# Microprocessor.net
KiCad netlist of a schematic drawn in Altium Designer
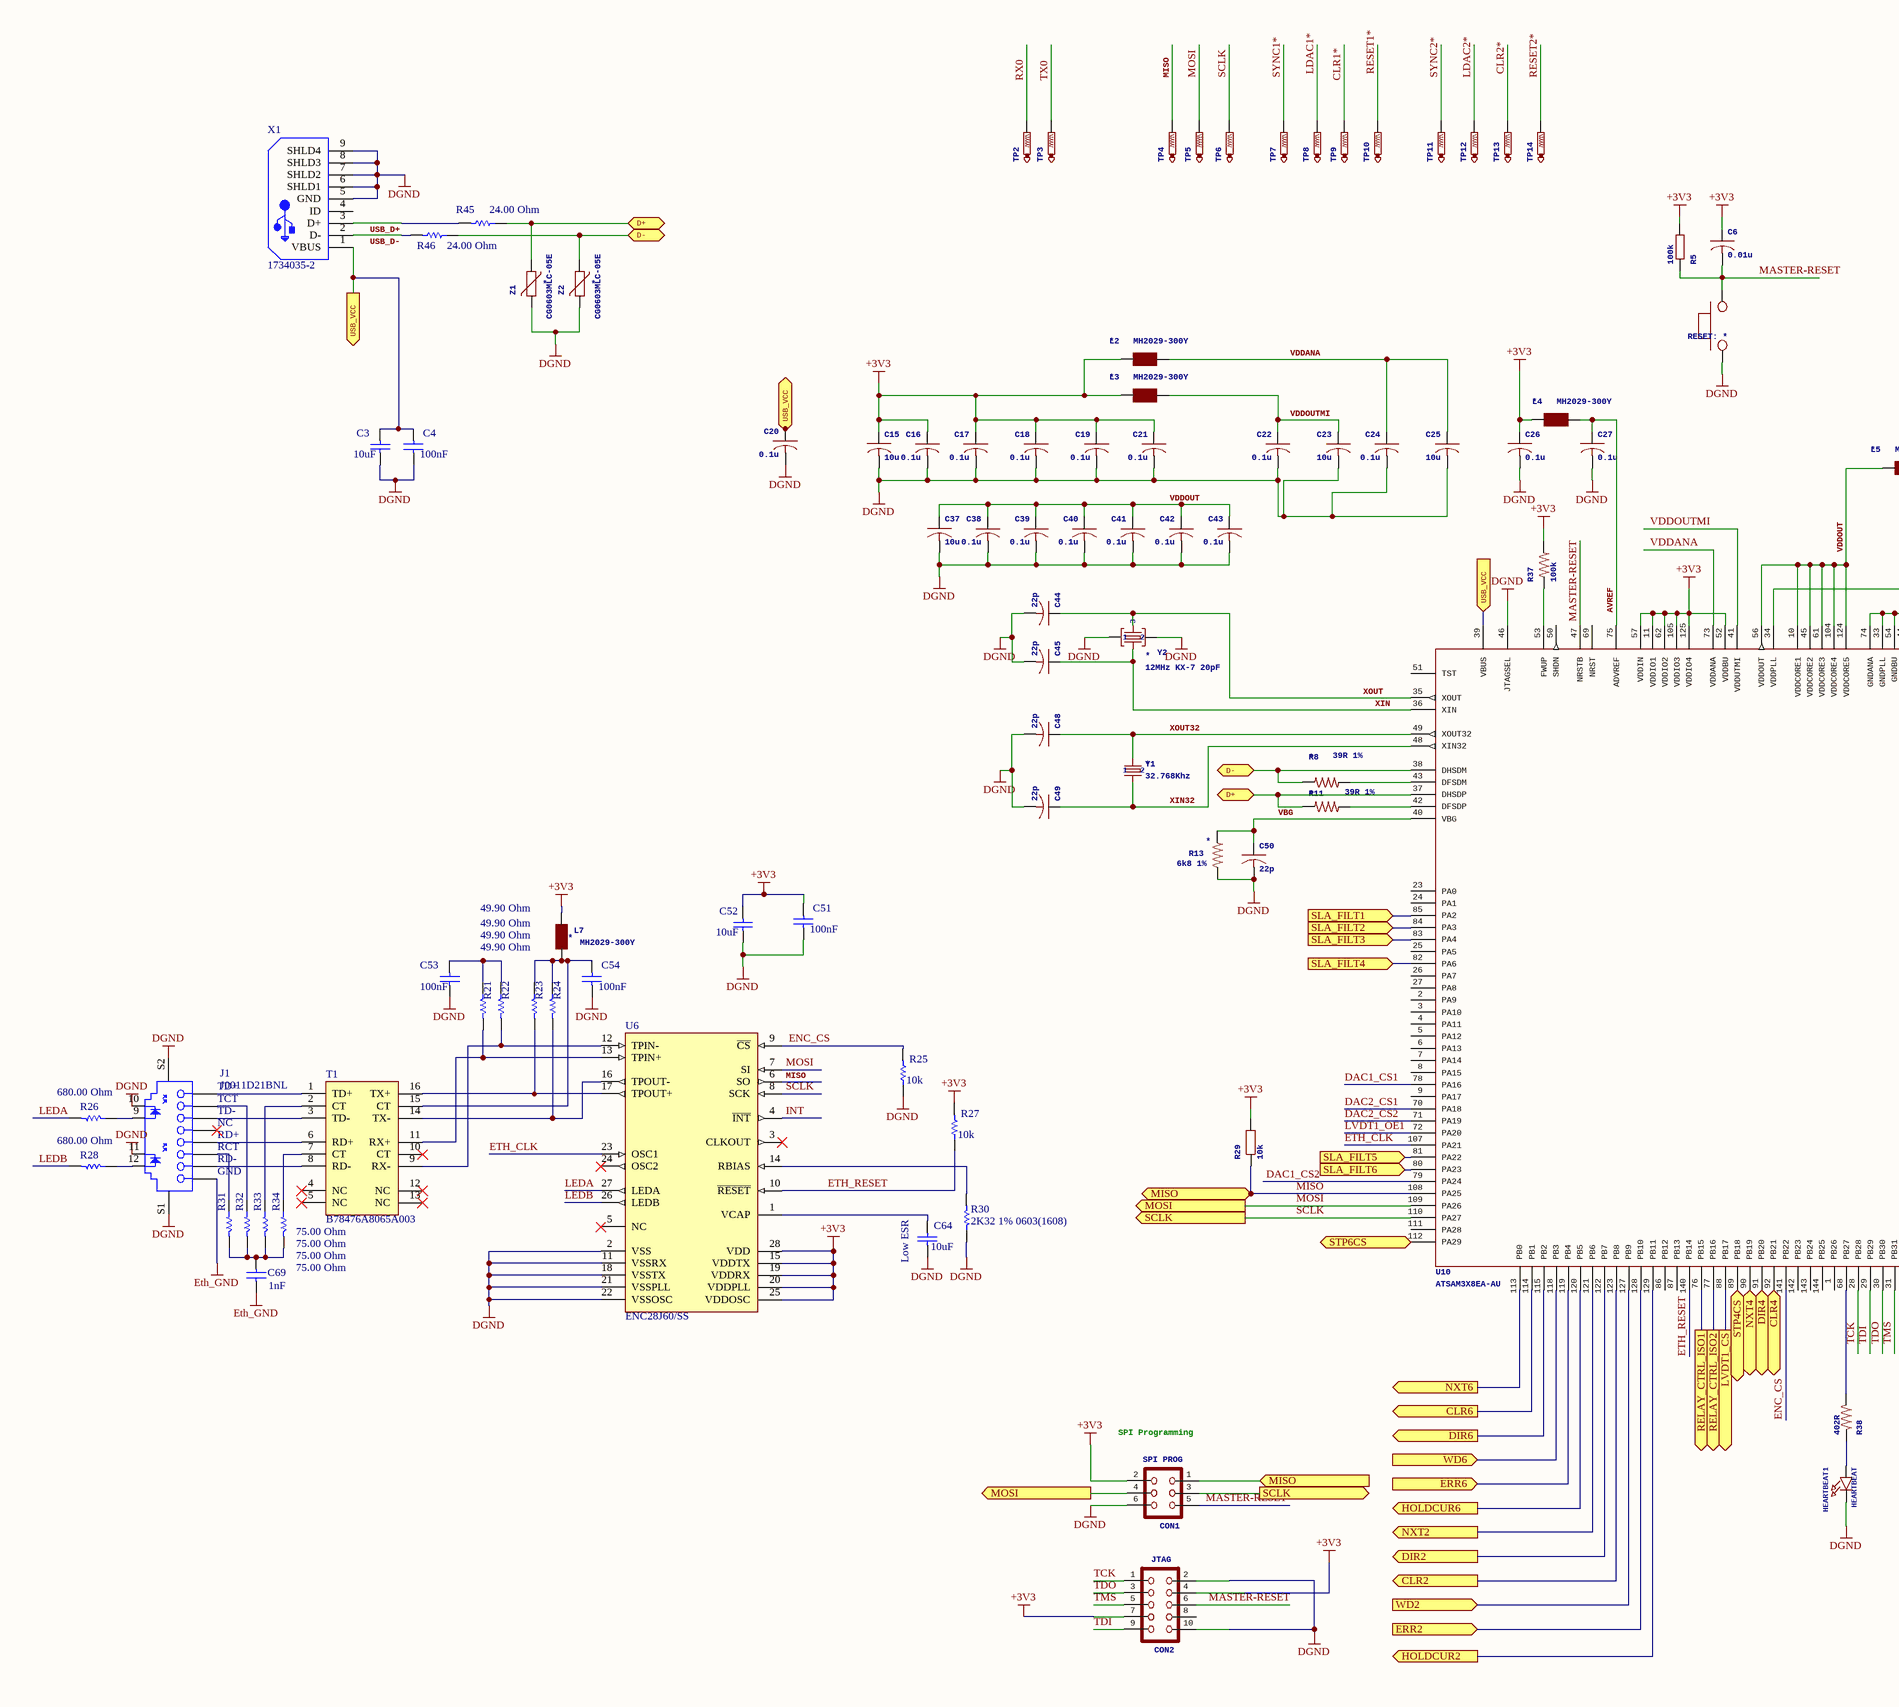
[diagram p0: Microprocessor.SchDoc, left]
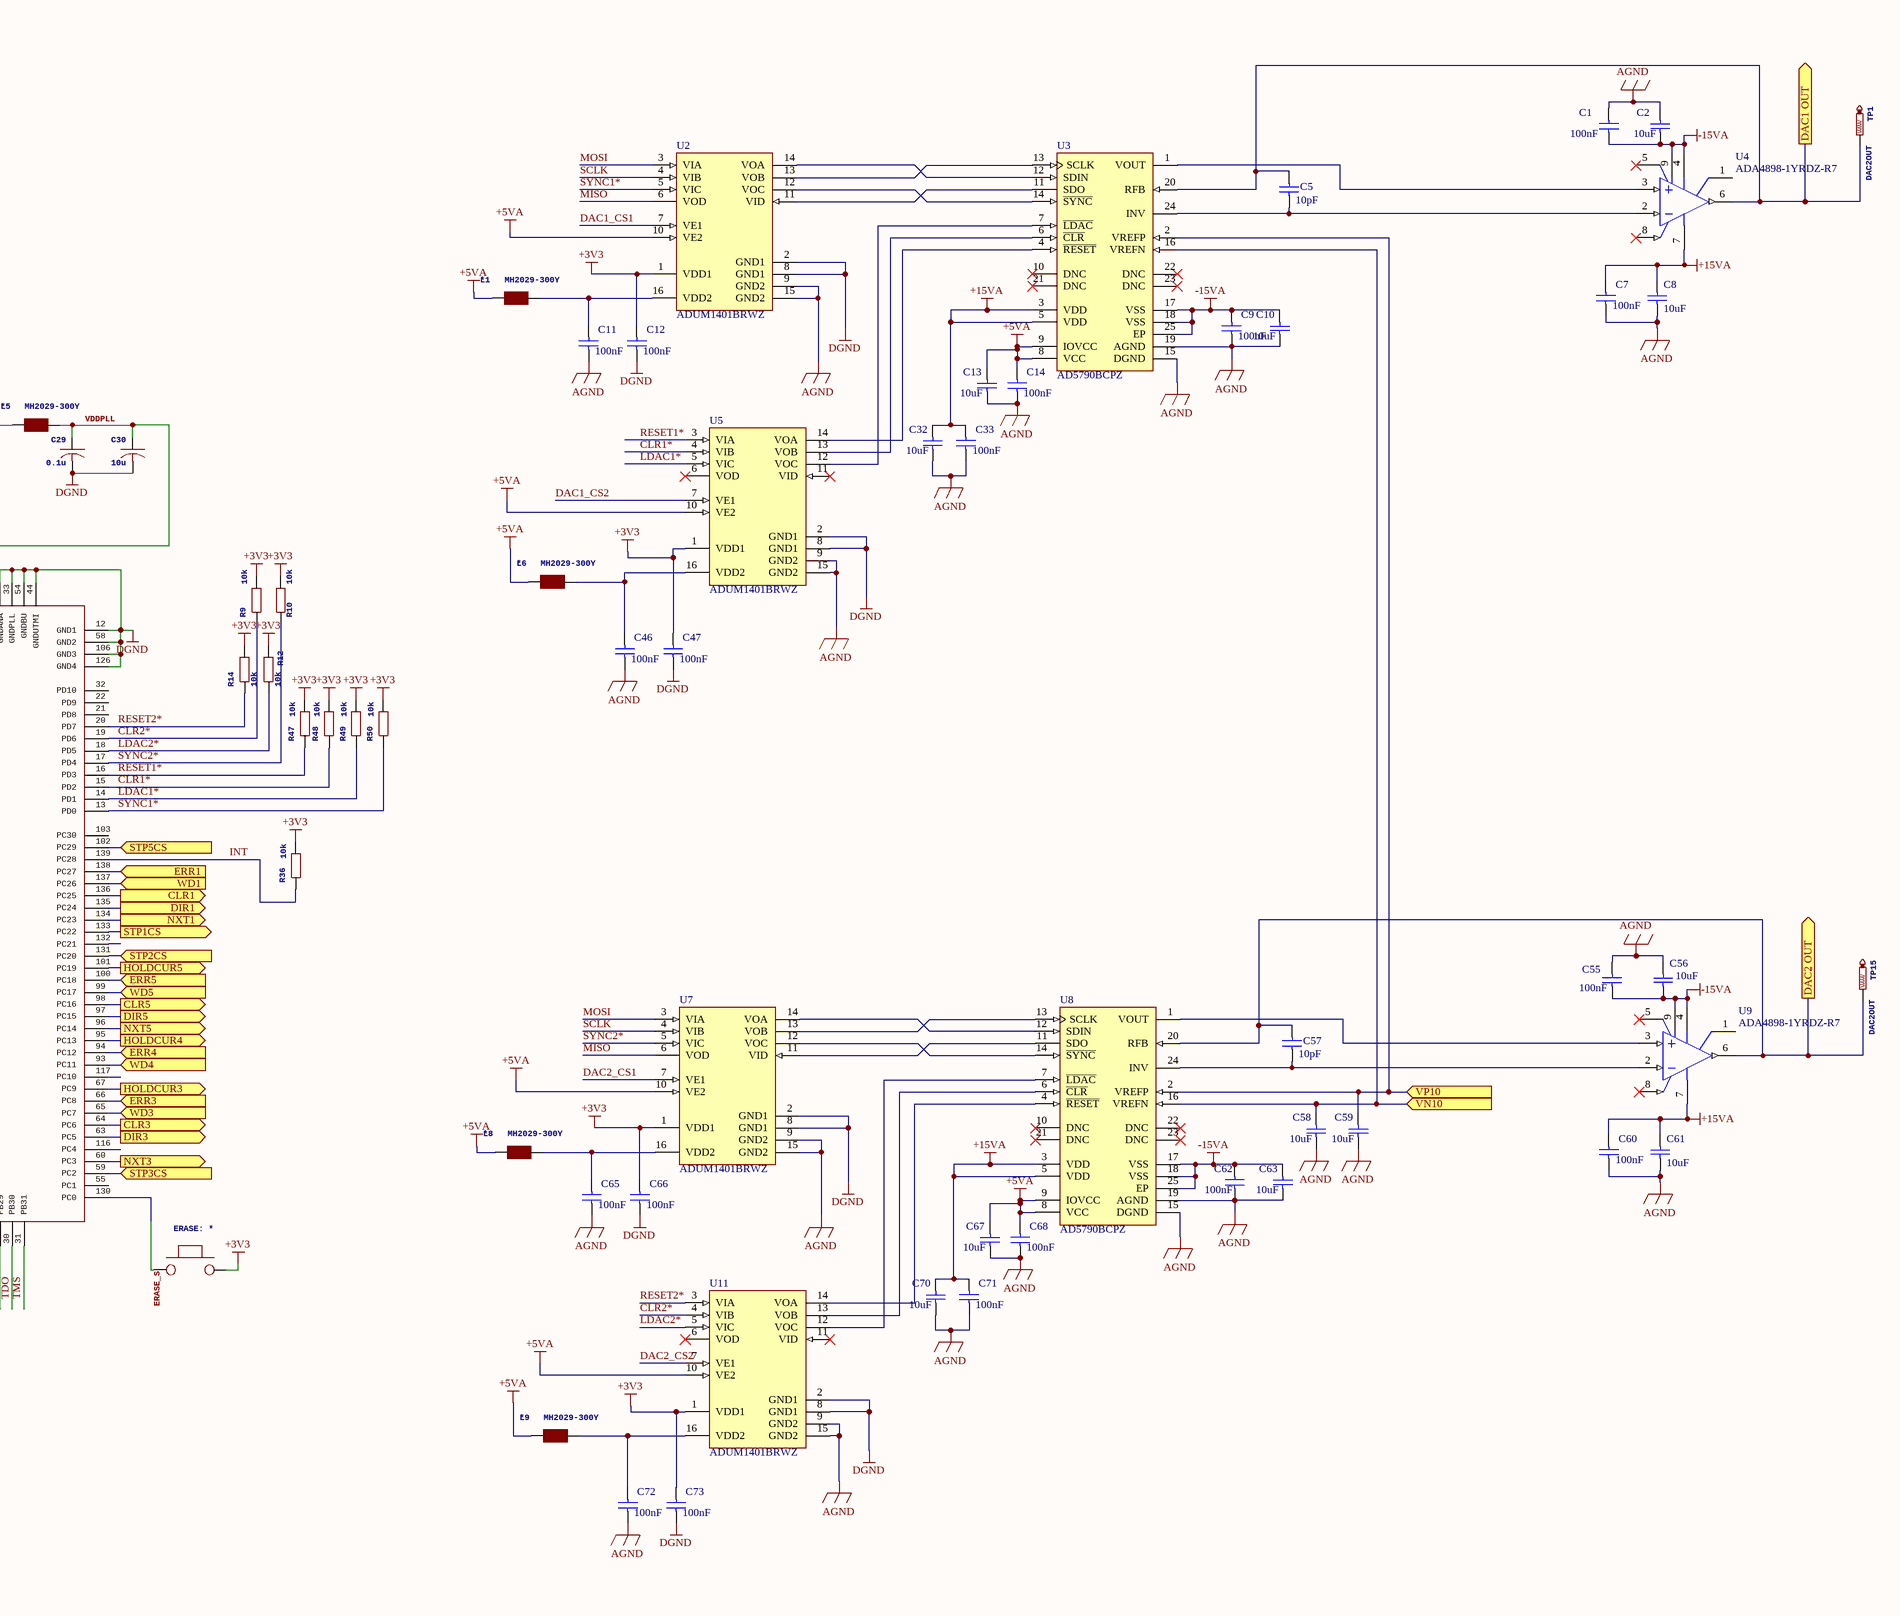
[diagram p1: Microprocessor.SchDoc, right]

(export (version "E")
  (design (tool "Eeschema 10.0.6"))
  (components
    (comp (ref "C1")
      (value "100nF")
      (footprint "CAPC0603(1608)100_N")
      (description "CAP 100nF 25V ±5% 0603 (1608 Metric) Thickness 1mm SMD")
      (fields (field (name "TOLERANCE") "Â±5%") (field (name "Comment") "CAP 100nF 25V 0603(1608)"))
      (libsource (lib "Altium Content Vault") (part "CMP-1035-02587-1"))
    )
    (comp (ref "C2")
      (value "10uF")
      (footprint "CAPC0805(2012)145_N")
      (description "CAP 10uF 6.3V -20% to +80% 0805 (2012 Metric) Thickness 1.45mm SMD")
      (fields (field (name "TOLERANCE") "-20% to +80%") (field (name "Comment") "CAP 10uF 6.3V 0805(2012)"))
      (libsource (lib "Altium Content Vault") (part "CMP-1036-04921-1"))
    )
    (comp (ref "C3")
      (value "10uF")
      (footprint "CAPC0805(2012)145_N")
      (description "CAP 10uF 6.3V -20% to +80% 0805 (2012 Metric) Thickness 1.45mm SMD")
      (fields (field (name "TOLERANCE") "-20% to +80%") (field (name "Comment") "CAP 10uF 6.3V 0805(2012)"))
      (libsource (lib "Altium Content Vault") (part "CMP-1036-04921-1"))
    )
    (comp (ref "C4")
      (value "100nF")
      (footprint "CAPC0603(1608)100_N")
      (description "CAP 100nF 25V ±5% 0603 (1608 Metric) Thickness 1mm SMD")
      (fields (field (name "TOLERANCE") "Â±5%") (field (name "Comment") "CAP 100nF 25V 0603(1608)"))
      (libsource (lib "Altium Content Vault") (part "CMP-1035-02587-1"))
    )
    (comp (ref "C5")
      (value "10pF")
      (footprint "CAPC0805(2012)100_M")
      (description "CAP 10pF 25V ±0.25pF 0805 (2012 Metric) Thickness 1mm SMD")
      (fields (field (name "TOLERANCE") "Â±0.25pF") (field (name "Comment") "CAP 10pF 25V 0805(2012)"))
      (libsource (lib "Altium Content Vault") (part "CMP-1036-00839-1"))
    )
    (comp (ref "C6")
      (value "0.01u")
      (footprint "C0805")
      (description "CAPACITOR, American symbol")
      (libsource (lib "") (part "C-USC0805_1"))
    )
    (comp (ref "C7")
      (value "100nF")
      (footprint "CAPC0603(1608)100_N")
      (description "CAP 100nF 25V ±5% 0603 (1608 Metric) Thickness 1mm SMD")
      (fields (field (name "TOLERANCE") "Â±5%") (field (name "Comment") "CAP 100nF 25V 0603(1608)"))
      (libsource (lib "Altium Content Vault") (part "CMP-1035-02587-1"))
    )
    (comp (ref "C8")
      (value "10uF")
      (footprint "CAPC0805(2012)145_N")
      (description "CAP 10uF 6.3V -20% to +80% 0805 (2012 Metric) Thickness 1.45mm SMD")
      (fields (field (name "TOLERANCE") "-20% to +80%") (field (name "Comment") "CAP 10uF 6.3V 0805(2012)"))
      (libsource (lib "Altium Content Vault") (part "CMP-1036-04921-1"))
    )
    (comp (ref "C9")
      (value "100nF")
      (footprint "CAPC0603(1608)100_N")
      (description "CAP 100nF 25V ±5% 0603 (1608 Metric) Thickness 1mm SMD")
      (fields (field (name "TOLERANCE") "Â±5%") (field (name "Comment") "CAP 100nF 25V 0603(1608)"))
      (libsource (lib "Altium Content Vault") (part "CMP-1035-02587-1"))
    )
    (comp (ref "C10")
      (value "10uF")
      (footprint "CAPC0805(2012)145_N")
      (description "CAP 10uF 6.3V -20% to +80% 0805 (2012 Metric) Thickness 1.45mm SMD")
      (fields (field (name "TOLERANCE") "-20% to +80%") (field (name "Comment") "CAP 10uF 6.3V 0805(2012)"))
      (libsource (lib "Altium Content Vault") (part "CMP-1036-04921-1"))
    )
    (comp (ref "C11")
      (value "100nF")
      (footprint "CAPC0603(1608)100_N")
      (description "CAP 100nF 25V ±5% 0603 (1608 Metric) Thickness 1mm SMD")
      (fields (field (name "TOLERANCE") "Â±5%") (field (name "Comment") "CAP 100nF 25V 0603(1608)"))
      (libsource (lib "Altium Content Vault") (part "CMP-1035-02587-1"))
    )
    (comp (ref "C12")
      (value "100nF")
      (footprint "CAPC0603(1608)100_N")
      (description "CAP 100nF 25V ±5% 0603 (1608 Metric) Thickness 1mm SMD")
      (fields (field (name "TOLERANCE") "Â±5%") (field (name "Comment") "CAP 100nF 25V 0603(1608)"))
      (libsource (lib "Altium Content Vault") (part "CMP-1035-02587-1"))
    )
    (comp (ref "C13")
      (value "10uF")
      (footprint "CAPC0805(2012)145_N")
      (description "CAP 10uF 6.3V -20% to +80% 0805 (2012 Metric) Thickness 1.45mm SMD")
      (fields (field (name "TOLERANCE") "-20% to +80%") (field (name "Comment") "CAP 10uF 6.3V 0805(2012)"))
      (libsource (lib "Altium Content Vault") (part "CMP-1036-04921-1"))
    )
    (comp (ref "C14")
      (value "100nF")
      (footprint "CAPC0603(1608)100_N")
      (description "CAP 100nF 25V ±5% 0603 (1608 Metric) Thickness 1mm SMD")
      (fields (field (name "TOLERANCE") "Â±5%") (field (name "Comment") "CAP 100nF 25V 0603(1608)"))
      (libsource (lib "Altium Content Vault") (part "CMP-1035-02587-1"))
    )
    (comp (ref "C15")
      (value "10u")
      (footprint "C0805")
      (description "CAPACITOR, American symbol")
      (libsource (lib "") (part "C-USC0805_1"))
    )
    (comp (ref "C16")
      (value "0.1u")
      (footprint "C0805")
      (description "CAPACITOR, American symbol")
      (libsource (lib "rcl") (part "C-USC0805"))
    )
    (comp (ref "C17")
      (value "0.1u")
      (footprint "C0805")
      (description "CAPACITOR, American symbol")
      (libsource (lib "rcl") (part "C-USC0805"))
    )
    (comp (ref "C18")
      (value "0.1u")
      (footprint "C0805")
      (description "CAPACITOR, American symbol")
      (libsource (lib "rcl") (part "C-USC0805"))
    )
    (comp (ref "C19")
      (value "0.1u")
      (footprint "C0805")
      (description "CAPACITOR, American symbol")
      (libsource (lib "rcl") (part "C-USC0805"))
    )
    (comp (ref "C20")
      (value "0.1u")
      (footprint "C0805")
      (description "CAPACITOR, American symbol")
      (libsource (lib "rcl") (part "C-USC0805"))
    )
    (comp (ref "C21")
      (value "0.1u")
      (footprint "C0805")
      (description "CAPACITOR, American symbol")
      (libsource (lib "rcl") (part "C-USC0805"))
    )
    (comp (ref "C22")
      (value "0.1u")
      (footprint "C0805")
      (description "CAPACITOR, American symbol")
      (libsource (lib "rcl") (part "C-USC0805"))
    )
    (comp (ref "C23")
      (value "10u")
      (footprint "C0805")
      (description "CAPACITOR, American symbol")
      (libsource (lib "rcl") (part "C-USC0805"))
    )
    (comp (ref "C24")
      (value "0.1u")
      (footprint "C0805")
      (description "CAPACITOR, American symbol")
      (libsource (lib "rcl") (part "C-USC0805"))
    )
    (comp (ref "C25")
      (value "10u")
      (footprint "C0805")
      (description "CAPACITOR, American symbol")
      (libsource (lib "rcl") (part "C-USC0805"))
    )
    (comp (ref "C26")
      (value "0.1u")
      (footprint "C0805")
      (description "CAPACITOR, American symbol")
      (libsource (lib "") (part "C-USC0805_1"))
    )
    (comp (ref "C27")
      (value "0.1u")
      (footprint "C0805")
      (description "CAPACITOR, American symbol")
      (libsource (lib "") (part "C-USC0805_1"))
    )
    (comp (ref "C29")
      (value "0.1u")
      (footprint "C0805")
      (description "CAPACITOR, American symbol")
      (libsource (lib "rcl") (part "C-USC0805"))
    )
    (comp (ref "C30")
      (value "10u")
      (footprint "C0805")
      (description "CAPACITOR, American symbol")
      (libsource (lib "rcl") (part "C-USC0805"))
    )
    (comp (ref "C32")
      (value "10uF")
      (footprint "CAPC0805(2012)145_N")
      (description "CAP 10uF 6.3V -20% to +80% 0805 (2012 Metric) Thickness 1.45mm SMD")
      (fields (field (name "TOLERANCE") "-20% to +80%") (field (name "Comment") "CAP 10uF 6.3V 0805(2012)"))
      (libsource (lib "Altium Content Vault") (part "CMP-1036-04921-1"))
    )
    (comp (ref "C33")
      (value "100nF")
      (footprint "CAPC0603(1608)100_N")
      (description "CAP 100nF 25V ±5% 0603 (1608 Metric) Thickness 1mm SMD")
      (fields (field (name "TOLERANCE") "Â±5%") (field (name "Comment") "CAP 100nF 25V 0603(1608)"))
      (libsource (lib "Altium Content Vault") (part "CMP-1035-02587-1"))
    )
    (comp (ref "C37")
      (value "10u")
      (footprint "C0805")
      (description "CAPACITOR, American symbol")
      (libsource (lib "") (part "C-USC0805_1"))
    )
    (comp (ref "C38")
      (value "0.1u")
      (footprint "C0805")
      (description "CAPACITOR, American symbol")
      (libsource (lib "rcl") (part "C-USC0805"))
    )
    (comp (ref "C39")
      (value "0.1u")
      (footprint "C0805")
      (description "CAPACITOR, American symbol")
      (libsource (lib "rcl") (part "C-USC0805"))
    )
    (comp (ref "C40")
      (value "0.1u")
      (footprint "C0805")
      (description "CAPACITOR, American symbol")
      (libsource (lib "rcl") (part "C-USC0805"))
    )
    (comp (ref "C41")
      (value "0.1u")
      (footprint "C0805")
      (description "CAPACITOR, American symbol")
      (libsource (lib "rcl") (part "C-USC0805"))
    )
    (comp (ref "C42")
      (value "0.1u")
      (footprint "C0805")
      (description "CAPACITOR, American symbol")
      (libsource (lib "rcl") (part "C-USC0805"))
    )
    (comp (ref "C43")
      (value "0.1u")
      (footprint "C0805")
      (description "CAPACITOR, American symbol")
      (libsource (lib "rcl") (part "C-USC0805"))
    )
    (comp (ref "C44")
      (value "22p")
      (footprint "C1206")
      (description "CAPACITOR, American symbol")
      (libsource (lib "rcl") (part "C-USC1206"))
    )
    (comp (ref "C45")
      (value "22p")
      (footprint "C1206")
      (description "CAPACITOR, American symbol")
      (libsource (lib "rcl") (part "C-USC1206"))
    )
    (comp (ref "C46")
      (value "100nF")
      (footprint "CAPC0603(1608)100_N")
      (description "CAP 100nF 25V ±5% 0603 (1608 Metric) Thickness 1mm SMD")
      (fields (field (name "TOLERANCE") "Â±5%") (field (name "Comment") "CAP 100nF 25V 0603(1608)"))
      (libsource (lib "Altium Content Vault") (part "CMP-1035-02587-1"))
    )
    (comp (ref "C47")
      (value "100nF")
      (footprint "CAPC0603(1608)100_N")
      (description "CAP 100nF 25V ±5% 0603 (1608 Metric) Thickness 1mm SMD")
      (fields (field (name "TOLERANCE") "Â±5%") (field (name "Comment") "CAP 100nF 25V 0603(1608)"))
      (libsource (lib "Altium Content Vault") (part "CMP-1035-02587-1"))
    )
    (comp (ref "C48")
      (value "22p")
      (footprint "C0805")
      (description "CAPACITOR, American symbol")
      (libsource (lib "rcl") (part "C-USC0805"))
    )
    (comp (ref "C49")
      (value "22p")
      (footprint "C0805")
      (description "CAPACITOR, American symbol")
      (libsource (lib "rcl") (part "C-USC0805"))
    )
    (comp (ref "C50")
      (value "22p")
      (footprint "C0805")
      (description "CAPACITOR, American symbol")
      (libsource (lib "") (part "C-USC0805_1"))
    )
    (comp (ref "C51")
      (value "100nF")
      (footprint "CAPC0603(1608)100_N")
      (description "CAP 100nF 25V ±5% 0603 (1608 Metric) Thickness 1mm SMD")
      (fields (field (name "TOLERANCE") "Â±5%") (field (name "Comment") "CAP 100nF 25V 0603(1608)"))
      (libsource (lib "Altium Content Vault") (part "CMP-1035-02587-1"))
    )
    (comp (ref "C52")
      (value "10uF")
      (footprint "CAPC0805(2012)145_N")
      (description "CAP 10uF 6.3V -20% to +80% 0805 (2012 Metric) Thickness 1.45mm SMD")
      (fields (field (name "TOLERANCE") "-20% to +80%") (field (name "Comment") "CAP 10uF 6.3V 0805(2012)"))
      (libsource (lib "Altium Content Vault") (part "CMP-1036-04921-1"))
    )
    (comp (ref "C53")
      (value "100nF")
      (footprint "CAPC0603(1608)100_N")
      (description "CAP 100nF 25V ±5% 0603 (1608 Metric) Thickness 1mm SMD")
      (fields (field (name "TOLERANCE") "Â±5%") (field (name "Comment") "CAP 100nF 25V 0603(1608)"))
      (libsource (lib "Altium Content Vault") (part "CMP-1035-02587-1"))
    )
    (comp (ref "C54")
      (value "100nF")
      (footprint "CAPC0603(1608)100_N")
      (description "CAP 100nF 25V ±5% 0603 (1608 Metric) Thickness 1mm SMD")
      (fields (field (name "TOLERANCE") "Â±5%") (field (name "Comment") "CAP 100nF 25V 0603(1608)"))
      (libsource (lib "Altium Content Vault") (part "CMP-1035-02587-1"))
    )
    (comp (ref "C55")
      (value "100nF")
      (footprint "CAPC0603(1608)100_N")
      (description "CAP 100nF 25V ±5% 0603 (1608 Metric) Thickness 1mm SMD")
      (fields (field (name "TOLERANCE") "Â±5%") (field (name "Comment") "CAP 100nF 25V 0603(1608)"))
      (libsource (lib "Altium Content Vault") (part "CMP-1035-02587-1"))
    )
    (comp (ref "C56")
      (value "10uF")
      (footprint "CAPC0805(2012)145_N")
      (description "CAP 10uF 6.3V -20% to +80% 0805 (2012 Metric) Thickness 1.45mm SMD")
      (fields (field (name "TOLERANCE") "-20% to +80%") (field (name "Comment") "CAP 10uF 6.3V 0805(2012)"))
      (libsource (lib "Altium Content Vault") (part "CMP-1036-04921-1"))
    )
    (comp (ref "C57")
      (value "10pF")
      (footprint "CAPC0805(2012)100_M")
      (description "CAP 10pF 25V ±0.25pF 0805 (2012 Metric) Thickness 1mm SMD")
      (fields (field (name "TOLERANCE") "Â±0.25pF") (field (name "Comment") "CAP 10pF 25V 0805(2012)"))
      (libsource (lib "Altium Content Vault") (part "CMP-1036-00839-1"))
    )
    (comp (ref "C58")
      (value "10uF")
      (footprint "CAPC0805(2012)145_N")
      (description "CAP 10uF 6.3V -20% to +80% 0805 (2012 Metric) Thickness 1.45mm SMD")
      (fields (field (name "TOLERANCE") "-20% to +80%") (field (name "Comment") "CAP 10uF 6.3V 0805(2012)"))
      (libsource (lib "Altium Content Vault") (part "CMP-1036-04921-1"))
    )
    (comp (ref "C59")
      (value "10uF")
      (footprint "CAPC0805(2012)145_N")
      (description "CAP 10uF 6.3V -20% to +80% 0805 (2012 Metric) Thickness 1.45mm SMD")
      (fields (field (name "TOLERANCE") "-20% to +80%") (field (name "Comment") "CAP 10uF 6.3V 0805(2012)"))
      (libsource (lib "Altium Content Vault") (part "CMP-1036-04921-1"))
    )
    (comp (ref "C60")
      (value "100nF")
      (footprint "CAPC0603(1608)100_N")
      (description "CAP 100nF 25V ±5% 0603 (1608 Metric) Thickness 1mm SMD")
      (fields (field (name "TOLERANCE") "Â±5%") (field (name "Comment") "CAP 100nF 25V 0603(1608)"))
      (libsource (lib "Altium Content Vault") (part "CMP-1035-02587-1"))
    )
    (comp (ref "C61")
      (value "10uF")
      (footprint "CAPC0805(2012)145_N")
      (description "CAP 10uF 6.3V -20% to +80% 0805 (2012 Metric) Thickness 1.45mm SMD")
      (fields (field (name "TOLERANCE") "-20% to +80%") (field (name "Comment") "CAP 10uF 6.3V 0805(2012)"))
      (libsource (lib "Altium Content Vault") (part "CMP-1036-04921-1"))
    )
    (comp (ref "C62")
      (value "100nF")
      (footprint "CAPC0603(1608)100_N")
      (description "CAP 100nF 25V ±5% 0603 (1608 Metric) Thickness 1mm SMD")
      (fields (field (name "TOLERANCE") "Â±5%") (field (name "Comment") "CAP 100nF 25V 0603(1608)"))
      (libsource (lib "Altium Content Vault") (part "CMP-1035-02587-1"))
    )
    (comp (ref "C63")
      (value "10uF")
      (footprint "CAPC0805(2012)145_N")
      (description "CAP 10uF 6.3V -20% to +80% 0805 (2012 Metric) Thickness 1.45mm SMD")
      (fields (field (name "TOLERANCE") "-20% to +80%") (field (name "Comment") "CAP 10uF 6.3V 0805(2012)"))
      (libsource (lib "Altium Content Vault") (part "CMP-1036-04921-1"))
    )
    (comp (ref "C64")
      (value "10uF")
      (footprint "CAPC1206(3216)190_M")
      (description "CAP 10uF 6.3V -20% to +80% 1206 (3216 Metric) Thickness 1.9mm SMD")
      (fields (field (name "TOLERANCE") "-20% to +80%") (field (name "Comment") "CAP 10uF 6.3V 1206(3216)"))
      (libsource (lib "Altium Content Vault") (part "CMP-1037-04965-1"))
    )
    (comp (ref "C65")
      (value "100nF")
      (footprint "CAPC0603(1608)100_N")
      (description "CAP 100nF 25V ±5% 0603 (1608 Metric) Thickness 1mm SMD")
      (fields (field (name "TOLERANCE") "Â±5%") (field (name "Comment") "CAP 100nF 25V 0603(1608)"))
      (libsource (lib "Altium Content Vault") (part "CMP-1035-02587-1"))
    )
    (comp (ref "C66")
      (value "100nF")
      (footprint "CAPC0603(1608)100_N")
      (description "CAP 100nF 25V ±5% 0603 (1608 Metric) Thickness 1mm SMD")
      (fields (field (name "TOLERANCE") "Â±5%") (field (name "Comment") "CAP 100nF 25V 0603(1608)"))
      (libsource (lib "Altium Content Vault") (part "CMP-1035-02587-1"))
    )
    (comp (ref "C67")
      (value "10uF")
      (footprint "CAPC0805(2012)145_N")
      (description "CAP 10uF 6.3V -20% to +80% 0805 (2012 Metric) Thickness 1.45mm SMD")
      (fields (field (name "TOLERANCE") "-20% to +80%") (field (name "Comment") "CAP 10uF 6.3V 0805(2012)"))
      (libsource (lib "Altium Content Vault") (part "CMP-1036-04921-1"))
    )
    (comp (ref "C68")
      (value "100nF")
      (footprint "CAPC0603(1608)100_N")
      (description "CAP 100nF 25V ±5% 0603 (1608 Metric) Thickness 1mm SMD")
      (fields (field (name "TOLERANCE") "Â±5%") (field (name "Comment") "CAP 100nF 25V 0603(1608)"))
      (libsource (lib "Altium Content Vault") (part "CMP-1035-02587-1"))
    )
    (comp (ref "C69")
      (value "1206GC102KAZ1A")
      (footprint "CAPC3317X180X60LL30T20")
      (description "Chip Capacitor, 1 nF, +/- 10%, 2000 V, -55 to 125 degC, 1206 (3216 Metric), RoHS, Tape and Reel")
      (fields (field (name "MANUFACTURER") "AVX") (field (name "CAPACITANCE") "1nF"))
      (libsource (lib "Altium Content Vault") (part "CMP-2000-05469-1"))
    )
    (comp (ref "C70")
      (value "10uF")
      (footprint "CAPC0805(2012)145_N")
      (description "CAP 10uF 6.3V -20% to +80% 0805 (2012 Metric) Thickness 1.45mm SMD")
      (fields (field (name "TOLERANCE") "-20% to +80%") (field (name "Comment") "CAP 10uF 6.3V 0805(2012)"))
      (libsource (lib "Altium Content Vault") (part "CMP-1036-04921-1"))
    )
    (comp (ref "C71")
      (value "100nF")
      (footprint "CAPC0603(1608)100_N")
      (description "CAP 100nF 25V ±5% 0603 (1608 Metric) Thickness 1mm SMD")
      (fields (field (name "TOLERANCE") "Â±5%") (field (name "Comment") "CAP 100nF 25V 0603(1608)"))
      (libsource (lib "Altium Content Vault") (part "CMP-1035-02587-1"))
    )
    (comp (ref "C72")
      (value "100nF")
      (footprint "CAPC0603(1608)100_N")
      (description "CAP 100nF 25V ±5% 0603 (1608 Metric) Thickness 1mm SMD")
      (fields (field (name "TOLERANCE") "Â±5%") (field (name "Comment") "CAP 100nF 25V 0603(1608)"))
      (libsource (lib "Altium Content Vault") (part "CMP-1035-02587-1"))
    )
    (comp (ref "C73")
      (value "100nF")
      (footprint "CAPC0603(1608)100_N")
      (description "CAP 100nF 25V ±5% 0603 (1608 Metric) Thickness 1mm SMD")
      (fields (field (name "TOLERANCE") "Â±5%") (field (name "Comment") "CAP 100nF 25V 0603(1608)"))
      (libsource (lib "Altium Content Vault") (part "CMP-1035-02587-1"))
    )
    (comp (ref "CON1")
      (value "SPI PROG")
      (footprint "CON06")
      (description "CONNECTOR")
      (libsource (lib "con-harting") (part "CON06"))
    )
    (comp (ref "CON2")
      (value "JTAG")
      (footprint "CON10")
      (description "CONNECTOR")
      (libsource (lib "con-harting") (part "CON10"))
    )
    (comp (ref "ERASE1")
      (value "PUCHBUTTON")
      (footprint "PUCHBUTTON")
      (fields (field (name "ERASE") "*"))
      (libsource (lib "PushButton") (part "PUCHBUTTON"))
    )
    (comp (ref "HEARTBEAT1")
      (value "HEARTBEAT")
      (footprint "CHIPLED_0805")
      (libsource (lib "microbuilder") (part "LED0805"))
    )
    (comp (ref "J1")
      (value "J0011D21BNL")
      (footprint "PULS-J00XXD21XNL-B-12")
      (fields (field (name "MANUFACTURER") "Pulse"))
      (libsource (lib "Altium Content Vault") (part "CMP-2000-05321-1"))
    )
    (comp (ref "L1")
      (value "MH2029-300Y")
      (footprint "0805")
      (fields (field (name "NAME") "*"))
      (libsource (lib "") (part "WE-CBF_0805_1"))
    )
    (comp (ref "L2")
      (value "MH2029-300Y")
      (footprint "0805")
      (fields (field (name "NAME") "*"))
      (libsource (lib "") (part "WE-CBF_0805_1"))
    )
    (comp (ref "L3")
      (value "MH2029-300Y")
      (footprint "0805")
      (fields (field (name "NAME") "*"))
      (libsource (lib "") (part "WE-CBF_0805_1"))
    )
    (comp (ref "L4")
      (value "MH2029-300Y")
      (footprint "0805")
      (fields (field (name "NAME") "*"))
      (libsource (lib "") (part "WE-CBF_0805_1"))
    )
    (comp (ref "L5")
      (value "MH2029-300Y")
      (footprint "0805")
      (fields (field (name "NAME") "*"))
      (libsource (lib "") (part "WE-CBF_0805_1"))
    )
    (comp (ref "L6")
      (value "MH2029-300Y")
      (footprint "0805")
      (fields (field (name "NAME") "*"))
      (libsource (lib "") (part "WE-CBF_0805_1"))
    )
    (comp (ref "L7")
      (value "MH2029-300Y")
      (footprint "0805")
      (fields (field (name "NAME") "*"))
      (libsource (lib "wuerth-elektronik") (part "WE-CBF_0805"))
    )
    (comp (ref "L8")
      (value "MH2029-300Y")
      (footprint "0805")
      (fields (field (name "NAME") "*"))
      (libsource (lib "") (part "WE-CBF_0805_1"))
    )
    (comp (ref "L9")
      (value "MH2029-300Y")
      (footprint "0805")
      (fields (field (name "NAME") "*"))
      (libsource (lib "") (part "WE-CBF_0805_1"))
    )
    (comp (ref "R5")
      (value "100k")
      (footprint "R0603")
      (description "RESISTOR, European symbol")
      (libsource (lib "rcl") (part "R-EU_R0603"))
    )
    (comp (ref "R8")
      (value "39R 1%")
      (footprint "R0805")
      (description "RESISTOR, American symbol")
      (fields (field (name "NAME") "*"))
      (libsource (lib "rcl") (part "R-US_R0805"))
    )
    (comp (ref "R9")
      (value "10k")
      (footprint "R0603")
      (description "RESISTOR, European symbol")
      (libsource (lib "rcl") (part "R-EU_R0603"))
    )
    (comp (ref "R10")
      (value "10k")
      (footprint "R0603")
      (description "RESISTOR, European symbol")
      (libsource (lib "rcl") (part "R-EU_R0603"))
    )
    (comp (ref "R11")
      (value "39R 1%")
      (footprint "R0805")
      (description "RESISTOR, American symbol")
      (fields (field (name "NAME") "*"))
      (libsource (lib "rcl") (part "R-US_R0805"))
    )
    (comp (ref "R12")
      (value "10k")
      (footprint "R0603")
      (description "RESISTOR, European symbol")
      (libsource (lib "rcl") (part "R-EU_R0603"))
    )
    (comp (ref "R13")
      (value "6k8 1%")
      (footprint "R0805")
      (description "RESISTOR, American symbol")
      (fields (field (name "NAME") "*"))
      (libsource (lib "rcl") (part "R-US_R0805"))
    )
    (comp (ref "R14")
      (value "10k")
      (footprint "R0603")
      (description "RESISTOR, European symbol")
      (libsource (lib "rcl") (part "R-EU_R0603"))
    )
    (comp (ref "R21")
      (value "49.90 Ohm")
      (footprint "RESC0603(1608)_N")
      (description "49R9 0.1W 1% 0603 (1608 Metric)  SMD")
      (fields (field (name "POWER") "0.1 W") (field (name "TOLERANCE") "1 %"))
      (libsource (lib "Altium Content Vault") (part "CMP-1012-00363-1"))
    )
    (comp (ref "R22")
      (value "49.90 Ohm")
      (footprint "RESC0603(1608)_N")
      (description "49R9 0.1W 1% 0603 (1608 Metric)  SMD")
      (fields (field (name "POWER") "0.1 W") (field (name "TOLERANCE") "1 %"))
      (libsource (lib "Altium Content Vault") (part "CMP-1012-00363-1"))
    )
    (comp (ref "R23")
      (value "49.90 Ohm")
      (footprint "RESC0603(1608)_N")
      (description "49R9 0.1W 1% 0603 (1608 Metric)  SMD")
      (fields (field (name "POWER") "0.1 W") (field (name "TOLERANCE") "1 %"))
      (libsource (lib "Altium Content Vault") (part "CMP-1012-00363-1"))
    )
    (comp (ref "R24")
      (value "49.90 Ohm")
      (footprint "RESC0603(1608)_N")
      (description "49R9 0.1W 1% 0603 (1608 Metric)  SMD")
      (fields (field (name "POWER") "0.1 W") (field (name "TOLERANCE") "1 %"))
      (libsource (lib "Altium Content Vault") (part "CMP-1012-00363-1"))
    )
    (comp (ref "R25")
      (value "MCR03ERTF1002")
      (footprint "RESC1608X55X30LL10T20_A")
      (description "Chip Resistor, 10 KOhm, +/- 1%, 0.1 W, -55 to 155 degC, 0603 (1608 Metric), RoHS, Tape and Reel")
      (fields
        (field (name "TOLERANCE") "±1%")
        (field (name "RESISTANCE (OHMS)") "10k")
        (field (name "MANUFACTURER") "Rohm")
      )
      (libsource (lib "Altium Content Vault") (part "CMP-2000-06685-1"))
    )
    (comp (ref "R26")
      (value "680.00 Ohm")
      (footprint "RESC0603(1608)_N")
      (description "680R 0.1W 1% 0603 (1608 Metric)  SMD")
      (fields (field (name "TOLERANCE") "1 %") (field (name "POWER") "0.1 W"))
      (libsource (lib "Altium Content Vault") (part "CMP-1012-00491-1"))
    )
    (comp (ref "R27")
      (value "MCR03ERTF1002")
      (footprint "RESC1608X55X30LL10T20_A")
      (description "Chip Resistor, 10 KOhm, +/- 1%, 0.1 W, -55 to 155 degC, 0603 (1608 Metric), RoHS, Tape and Reel")
      (fields
        (field (name "TOLERANCE") "±1%")
        (field (name "RESISTANCE (OHMS)") "10k")
        (field (name "MANUFACTURER") "Rohm")
      )
      (libsource (lib "Altium Content Vault") (part "CMP-2000-06685-1"))
    )
    (comp (ref "R28")
      (value "680.00 Ohm")
      (footprint "RESC0603(1608)_N")
      (description "680R 0.1W 1% 0603 (1608 Metric)  SMD")
      (fields (field (name "TOLERANCE") "1 %") (field (name "POWER") "0.1 W"))
      (libsource (lib "Altium Content Vault") (part "CMP-1012-00491-1"))
    )
    (comp (ref "R29")
      (value "10k")
      (footprint "R0603")
      (description "RESISTOR, European symbol")
      (libsource (lib "rcl") (part "R-EU_R0603"))
    )
    (comp (ref "R30")
      (value "2K32 1% 0603(1608)")
      (footprint "RESC0603(1608)_L")
      (description "2K32 0.1W 1% 0603 (1608 Metric)  SMD")
      (fields (field (name "TOLERANCE") "1 %") (field (name "POWER") "0.1 W"))
      (libsource (lib "Altium Content Vault") (part "RES"))
    )
    (comp (ref "R31")
      (value "75.00 Ohm")
      (footprint "RESC0603(1608)_M")
      (description "75R 0.1W 1% 0603 (1608 Metric)  SMD")
      (fields (field (name "POWER") "0.1 W") (field (name "TOLERANCE") "1 %"))
      (libsource (lib "Altium Content Vault") (part "CMP-1012-00383-1"))
    )
    (comp (ref "R32")
      (value "75.00 Ohm")
      (footprint "RESC0603(1608)_M")
      (description "75R 0.1W 1% 0603 (1608 Metric)  SMD")
      (fields (field (name "POWER") "0.1 W") (field (name "TOLERANCE") "1 %"))
      (libsource (lib "Altium Content Vault") (part "CMP-1012-00383-1"))
    )
    (comp (ref "R33")
      (value "75.00 Ohm")
      (footprint "RESC0603(1608)_M")
      (description "75R 0.1W 1% 0603 (1608 Metric)  SMD")
      (fields (field (name "POWER") "0.1 W") (field (name "TOLERANCE") "1 %"))
      (libsource (lib "Altium Content Vault") (part "CMP-1012-00383-1"))
    )
    (comp (ref "R34")
      (value "75.00 Ohm")
      (footprint "RESC0603(1608)_M")
      (description "75R 0.1W 1% 0603 (1608 Metric)  SMD")
      (fields (field (name "POWER") "0.1 W") (field (name "TOLERANCE") "1 %"))
      (libsource (lib "Altium Content Vault") (part "CMP-1012-00383-1"))
    )
    (comp (ref "R36")
      (value "10k")
      (footprint "R0603")
      (description "RESISTOR, European symbol")
      (libsource (lib "rcl") (part "R-EU_R0603"))
    )
    (comp (ref "R37")
      (value "100k")
      (footprint "R0805")
      (description "RESISTOR, American symbol")
      (libsource (lib "rcl") (part "R-US_R0805"))
    )
    (comp (ref "R38")
      (value "402R")
      (footprint "R0805")
      (description "RESISTOR, American symbol")
      (libsource (lib "rcl") (part "R-US_R0805"))
    )
    (comp (ref "R45")
      (value "24.00 Ohm")
      (footprint "RESC0603(1608)_N")
      (description "24R 0.1W 5% 0603 (1608 Metric)  SMD")
      (fields (field (name "TOLERANCE") "5 %") (field (name "POWER") "0.1 W"))
      (libsource (lib "Altium Content Vault") (part "CMP-1012-00035-1"))
    )
    (comp (ref "R46")
      (value "24.00 Ohm")
      (footprint "RESC0603(1608)_N")
      (description "24R 0.1W 5% 0603 (1608 Metric)  SMD")
      (fields (field (name "TOLERANCE") "5 %") (field (name "POWER") "0.1 W"))
      (libsource (lib "Altium Content Vault") (part "CMP-1012-00035-1"))
    )
    (comp (ref "R47")
      (value "10k")
      (footprint "R0603")
      (description "RESISTOR, European symbol")
      (libsource (lib "rcl") (part "R-EU_R0603"))
    )
    (comp (ref "R48")
      (value "10k")
      (footprint "R0603")
      (description "RESISTOR, European symbol")
      (libsource (lib "rcl") (part "R-EU_R0603"))
    )
    (comp (ref "R49")
      (value "10k")
      (footprint "R0603")
      (description "RESISTOR, European symbol")
      (libsource (lib "rcl") (part "R-EU_R0603"))
    )
    (comp (ref "R50")
      (value "10k")
      (footprint "R0603")
      (description "RESISTOR, European symbol")
      (libsource (lib "rcl") (part "R-EU_R0603"))
    )
    (comp (ref "RESET1")
      (value "PUCHBUTTON")
      (footprint "PUCHBUTTON")
      (fields (field (name "RESET") "*"))
      (libsource (lib "PushButton") (part "PUCHBUTTON"))
    )
    (comp (ref "T1")
      (value "B78476A8065A003")
      (footprint "EPCS-B78476A8065A003-16")
      (fields (field (name "MANUFACTURER") "EPCOS"))
      (libsource (lib "Altium Content Vault") (part "EPCS-B78476A8065A003-16"))
    )
    (comp (ref "TP1")
      (value "PTR1PAD1-13")
      (footprint "P1-13")
      (description "TEST PIN")
      (fields (field (name "TP_SIGNAL_NAME") "DAC2OUT"))
      (libsource (lib "") (part "PTR1PAD1-13_1"))
    )
    (comp (ref "TP2")
      (value "PTR1PAD1-13")
      (footprint "P1-13")
      (description "TEST PIN")
      (libsource (lib "testpad") (part "PTR1PAD1-13"))
    )
    (comp (ref "TP3")
      (value "PTR1PAD1-13")
      (footprint "P1-13")
      (description "TEST PIN")
      (libsource (lib "testpad") (part "PTR1PAD1-13"))
    )
    (comp (ref "TP4")
      (value "PTR1PAD1-13")
      (footprint "P1-13")
      (description "TEST PIN")
      (libsource (lib "testpad") (part "PTR1PAD1-13"))
    )
    (comp (ref "TP5")
      (value "PTR1PAD1-13")
      (footprint "P1-13")
      (description "TEST PIN")
      (libsource (lib "testpad") (part "PTR1PAD1-13"))
    )
    (comp (ref "TP6")
      (value "PTR1PAD1-13")
      (footprint "P1-13")
      (description "TEST PIN")
      (libsource (lib "testpad") (part "PTR1PAD1-13"))
    )
    (comp (ref "TP7")
      (value "PTR1PAD1-13")
      (footprint "P1-13")
      (description "TEST PIN")
      (libsource (lib "testpad") (part "PTR1PAD1-13"))
    )
    (comp (ref "TP8")
      (value "PTR1PAD1-13")
      (footprint "P1-13")
      (description "TEST PIN")
      (libsource (lib "testpad") (part "PTR1PAD1-13"))
    )
    (comp (ref "TP9")
      (value "PTR1PAD1-13")
      (footprint "P1-13")
      (description "TEST PIN")
      (libsource (lib "testpad") (part "PTR1PAD1-13"))
    )
    (comp (ref "TP10")
      (value "PTR1PAD1-13")
      (footprint "P1-13")
      (description "TEST PIN")
      (libsource (lib "testpad") (part "PTR1PAD1-13"))
    )
    (comp (ref "TP11")
      (value "PTR1PAD1-13")
      (footprint "P1-13")
      (description "TEST PIN")
      (libsource (lib "testpad") (part "PTR1PAD1-13"))
    )
    (comp (ref "TP12")
      (value "PTR1PAD1-13")
      (footprint "P1-13")
      (description "TEST PIN")
      (libsource (lib "testpad") (part "PTR1PAD1-13"))
    )
    (comp (ref "TP13")
      (value "PTR1PAD1-13")
      (footprint "P1-13")
      (description "TEST PIN")
      (libsource (lib "testpad") (part "PTR1PAD1-13"))
    )
    (comp (ref "TP14")
      (value "PTR1PAD1-13")
      (footprint "P1-13")
      (description "TEST PIN")
      (libsource (lib "testpad") (part "PTR1PAD1-13"))
    )
    (comp (ref "TP15")
      (value "PTR1PAD1-13")
      (footprint "P1-13")
      (description "TEST PIN")
      (fields (field (name "TP_SIGNAL_NAME") "DAC2OUT"))
      (libsource (lib "") (part "PTR1PAD1-13_1"))
    )
    (comp (ref "U2")
      (value "ADUM1401BRWZ")
      (footprint "ADI-RW-16_M")
      (fields (field (name "MANUFACTURER") "Analog Devices"))
      (libsource (lib "Altium Content Vault") (part "ADI-ADUMX4X1-16"))
    )
    (comp (ref "U3")
      (value "AD5790BCPZ")
      (footprint "CP-24-5_N")
      (fields (field (name "MANUFACTURER") "Analog Devices") (field (name "GENERIC PART NUMBER") "AD5790"))
      (libsource (lib "Altium Content Vault") (part "CMP-0318-00532-2"))
    )
    (comp (ref "U4")
      (value "ADA4898-1YRDZ-R7")
      (footprint "ADI-RD-8-1_N")
      (fields (field (name "GENERIC PART NUMBER") "ADA4898-1") (field (name "MANUFACTURER") "Analog Devices"))
      (libsource (lib "Altium Content Vault") (part "CMP-0384-01432-1"))
    )
    (comp (ref "U5")
      (value "ADUM1401BRWZ")
      (footprint "ADI-RW-16_M")
      (fields (field (name "MANUFACTURER") "Analog Devices"))
      (libsource (lib "Altium Content Vault") (part "ADI-ADUMX4X1-16"))
    )
    (comp (ref "U6")
      (value "ENC28J60/SS")
      (footprint "SSOP-SS28_M")
      (description "Stand-Alone Ethernet Controller with SPI Interface, 28-Pin SSOP")
      (libsource (lib "Altium Content Vault") (part "CMP-0186-00068-2"))
    )
    (comp (ref "U7")
      (value "ADUM1401BRWZ")
      (footprint "ADI-RW-16_M")
      (fields (field (name "MANUFACTURER") "Analog Devices"))
      (libsource (lib "Altium Content Vault") (part "ADI-ADUMX4X1-16"))
    )
    (comp (ref "U8")
      (value "AD5790BCPZ")
      (footprint "CP-24-5_N")
      (fields (field (name "MANUFACTURER") "Analog Devices") (field (name "GENERIC PART NUMBER") "AD5790"))
      (libsource (lib "Altium Content Vault") (part "CMP-0318-00532-2"))
    )
    (comp (ref "U9")
      (value "ADA4898-1YRDZ-R7")
      (footprint "ADI-RD-8-1_N")
      (fields (field (name "GENERIC PART NUMBER") "ADA4898-1") (field (name "MANUFACTURER") "Analog Devices"))
      (libsource (lib "Altium Content Vault") (part "CMP-0384-01432-1"))
    )
    (comp (ref "U10")
      (value "ATSAM3X8EA-AU")
      (footprint "CurrentSource2:LQFP144")
      (libsource (lib "SmartPrj") (part "ATSAM3X/AAU"))
    )
    (comp (ref "U11")
      (value "ADUM1401BRWZ")
      (footprint "ADI-RW-16_M")
      (fields (field (name "MANUFACTURER") "Analog Devices"))
      (libsource (lib "Altium Content Vault") (part "ADI-ADUMX4X1-16"))
    )
    (comp (ref "X1")
      (value "1734035-2")
      (footprint "TECO-1734035-2-5_V")
      (description "Surface Mount Type B Mini USB, 5 Positions, 0.8 mm Pitch, 0 to 50 degC, RoHS, Tape and Reel")
      (fields (field (name "MANUFACTURER") "TE Connectivity"))
      (libsource (lib "Altium Content Vault") (part "USB-5-4SHLD"))
    )
    (comp (ref "Y1")
      (value "32.768Khz")
      (footprint "ARDUINO_WIFI_SHIELD_V018_TG_RESONATOR_EPSON_FC_145")
      (fields (field (name "NAME") "*") (field (name "1") "1") (field (name "2") "2"))
      (libsource (lib "Arduino_Wifi_shield_v018_tG") (part "ARDUINO_WIFI_SHIELD_V018_TG_RESONATOR_EPSON_FC_145"))
    )
    (comp (ref "Y2")
      (value "12MHz KX-7 20pF")
      (footprint "CRYSTAL-3.2-2.5")
      (fields (field (name "NAME") "*") (field (name "1") "1") (field (name "2") "2") (field (name "3") "3"))
      (libsource (lib "SmartPrj") (part "CRYSTAL-3.2-2.5"))
    )
    (comp (ref "Z1")
      (value "CG0603MLC-05E")
      (footprint "CT/CN0603")
      (description "VARISTOR")
      (fields (field (name "NAME") "*"))
      (libsource (lib "varistor") (part "VARISTORCN0603"))
    )
    (comp (ref "Z2")
      (value "CG0603MLC-05E")
      (footprint "CT/CN0603")
      (description "VARISTOR")
      (fields (field (name "NAME") "*"))
      (libsource (lib "varistor") (part "VARISTORCN0603"))
    )
  )
  (nets
    (net (code "1") (name "+3V3") (class "Default")
      (node (ref "C12") (pin "1") (pinfunction "1_1") (pintype "passive"))
      (node (ref "C15") (pin "1") (pinfunction "1_1") (pintype "passive"))
      (node (ref "C16") (pin "1") (pinfunction "1_1") (pintype "passive"))
      (node (ref "C17") (pin "1") (pinfunction "1_1") (pintype "passive"))
      (node (ref "C18") (pin "1") (pinfunction "1_1") (pintype "passive"))
      (node (ref "C19") (pin "1") (pinfunction "1_1") (pintype "passive"))
      (node (ref "C21") (pin "1") (pinfunction "1_1") (pintype "passive"))
      (node (ref "C26") (pin "1") (pinfunction "1_1") (pintype "passive"))
      (node (ref "C47") (pin "1") (pinfunction "1_1") (pintype "passive"))
      (node (ref "C51") (pin "1") (pinfunction "1_1") (pintype "passive"))
      (node (ref "C52") (pin "2") (pinfunction "2_2") (pintype "passive"))
      (node (ref "C6") (pin "1") (pinfunction "1_1") (pintype "passive"))
      (node (ref "C66") (pin "1") (pinfunction "1_1") (pintype "passive"))
      (node (ref "C73") (pin "1") (pinfunction "1_1") (pintype "passive"))
      (node (ref "CON1") (pin "2") (pinfunction "2_2") (pintype "passive"))
      (node (ref "CON2") (pin "4") (pinfunction "4_4") (pintype "passive"))
      (node (ref "CON2") (pin "7") (pinfunction "7_7") (pintype "passive"))
      (node (ref "ERASE1") (pin "P$2") (pinfunction "P$5_P$2") (pintype "passive"))
      (node (ref "L2") (pin "1") (pinfunction "1_1") (pintype "passive"))
      (node (ref "L3") (pin "1") (pinfunction "1_1") (pintype "passive"))
      (node (ref "L4") (pin "1") (pinfunction "1_1") (pintype "passive"))
      (node (ref "L7") (pin "1") (pinfunction "1_1") (pintype "passive"))
      (node (ref "R10") (pin "2") (pinfunction "2_2") (pintype "passive"))
      (node (ref "R12") (pin "2") (pinfunction "2_2") (pintype "passive"))
      (node (ref "R14") (pin "2") (pinfunction "2_2") (pintype "passive"))
      (node (ref "R27") (pin "2") (pinfunction "2_2") (pintype "passive"))
      (node (ref "R29") (pin "2") (pinfunction "2_2") (pintype "passive"))
      (node (ref "R36") (pin "2") (pinfunction "2_2") (pintype "passive"))
      (node (ref "R37") (pin "2") (pinfunction "2_2") (pintype "passive"))
      (node (ref "R47") (pin "2") (pinfunction "2_2") (pintype "passive"))
      (node (ref "R48") (pin "2") (pinfunction "2_2") (pintype "passive"))
      (node (ref "R49") (pin "2") (pinfunction "2_2") (pintype "passive"))
      (node (ref "R5") (pin "2") (pinfunction "2_2") (pintype "passive"))
      (node (ref "R50") (pin "2") (pinfunction "2_2") (pintype "passive"))
      (node (ref "R9") (pin "2") (pinfunction "2_2") (pintype "passive"))
      (node (ref "U10") (pin "105") (pinfunction "VDDIO3_105") (pintype "power_in"))
      (node (ref "U10") (pin "11") (pinfunction "VDDIO1_11") (pintype "power_in"))
      (node (ref "U10") (pin "125") (pinfunction "VDDIO4_125") (pintype "power_in"))
      (node (ref "U10") (pin "52") (pinfunction "VDDBU_52") (pintype "power_in"))
      (node (ref "U10") (pin "57") (pinfunction "VDDIN_57") (pintype "power_in"))
      (node (ref "U10") (pin "62") (pinfunction "VDDIO2_62") (pintype "power_in"))
      (node (ref "U11") (pin "1") (pinfunction "VDD1_1") (pintype "power_in"))
      (node (ref "U2") (pin "1") (pinfunction "VDD1_1") (pintype "power_in"))
      (node (ref "U5") (pin "1") (pinfunction "VDD1_1") (pintype "power_in"))
      (node (ref "U6") (pin "15") (pinfunction "VDDTX_15") (pintype "power_in"))
      (node (ref "U6") (pin "19") (pinfunction "VDDRX_19") (pintype "power_in"))
      (node (ref "U6") (pin "20") (pinfunction "VDDPLL_20") (pintype "power_in"))
      (node (ref "U6") (pin "25") (pinfunction "VDDOSC_25") (pintype "power_in"))
      (node (ref "U6") (pin "28") (pinfunction "VDD_28") (pintype "power_in"))
      (node (ref "U7") (pin "1") (pinfunction "VDD1_1") (pintype "power_in"))
    )
    (net (code "2") (name "+5VA") (class "Default")
      (node (ref "C13") (pin "2") (pinfunction "2_2") (pintype "passive"))
      (node (ref "C14") (pin "1") (pinfunction "1_1") (pintype "passive"))
      (node (ref "C67") (pin "2") (pinfunction "2_2") (pintype "passive"))
      (node (ref "C68") (pin "1") (pinfunction "1_1") (pintype "passive"))
      (node (ref "L1") (pin "1") (pinfunction "1_1") (pintype "passive"))
      (node (ref "L6") (pin "1") (pinfunction "1_1") (pintype "passive"))
      (node (ref "L8") (pin "1") (pinfunction "1_1") (pintype "passive"))
      (node (ref "L9") (pin "1") (pinfunction "1_1") (pintype "passive"))
      (node (ref "U11") (pin "10") (pinfunction "VE2_10") (pintype "input"))
      (node (ref "U2") (pin "10") (pinfunction "VE2_10") (pintype "input"))
      (node (ref "U3") (pin "8") (pinfunction "VCC_8") (pintype "power_in"))
      (node (ref "U3") (pin "9") (pinfunction "IOVCC_9") (pintype "power_in"))
      (node (ref "U5") (pin "10") (pinfunction "VE2_10") (pintype "input"))
      (node (ref "U7") (pin "10") (pinfunction "VE2_10") (pintype "input"))
      (node (ref "U8") (pin "8") (pinfunction "VCC_8") (pintype "power_in"))
      (node (ref "U8") (pin "9") (pinfunction "IOVCC_9") (pintype "power_in"))
    )
    (net (code "3") (name "+15VA") (class "Default")
      (node (ref "C32") (pin "2") (pinfunction "2_2") (pintype "passive"))
      (node (ref "C33") (pin "1") (pinfunction "1_1") (pintype "passive"))
      (node (ref "C60") (pin "1") (pinfunction "1_1") (pintype "passive"))
      (node (ref "C61") (pin "2") (pinfunction "2_2") (pintype "passive"))
      (node (ref "C7") (pin "1") (pinfunction "1_1") (pintype "passive"))
      (node (ref "C70") (pin "2") (pinfunction "2_2") (pintype "passive"))
      (node (ref "C71") (pin "1") (pinfunction "1_1") (pintype "passive"))
      (node (ref "C8") (pin "2") (pinfunction "2_2") (pintype "passive"))
      (node (ref "U3") (pin "3") (pinfunction "VDD_3") (pintype "power_in"))
      (node (ref "U3") (pin "5") (pinfunction "VDD_5") (pintype "power_in"))
      (node (ref "U4") (pin "7") (pinfunction "+VS_7") (pintype "power_in"))
      (node (ref "U8") (pin "3") (pinfunction "VDD_3") (pintype "power_in"))
      (node (ref "U8") (pin "5") (pinfunction "VDD_5") (pintype "power_in"))
      (node (ref "U9") (pin "7") (pinfunction "+VS_7") (pintype "power_in"))
    )
    (net (code "4") (name "-15VA") (class "Default")
      (node (ref "C1") (pin "2") (pinfunction "2_2") (pintype "passive"))
      (node (ref "C10") (pin "2") (pinfunction "2_2") (pintype "passive"))
      (node (ref "C2") (pin "1") (pinfunction "1_1") (pintype "passive"))
      (node (ref "C55") (pin "2") (pinfunction "2_2") (pintype "passive"))
      (node (ref "C56") (pin "1") (pinfunction "1_1") (pintype "passive"))
      (node (ref "C62") (pin "1") (pinfunction "1_1") (pintype "passive"))
      (node (ref "C63") (pin "2") (pinfunction "2_2") (pintype "passive"))
      (node (ref "C9") (pin "1") (pinfunction "1_1") (pintype "passive"))
      (node (ref "U3") (pin "17") (pinfunction "VSS_17") (pintype "power_in"))
      (node (ref "U3") (pin "18") (pinfunction "VSS_18") (pintype "power_in"))
      (node (ref "U3") (pin "25") (pinfunction "EP_25") (pintype "power_in"))
      (node (ref "U4") (pin "4") (pinfunction "-VS_4") (pintype "power_in"))
      (node (ref "U4") (pin "9") (pinfunction "EP_9") (pintype "passive"))
      (node (ref "U8") (pin "17") (pinfunction "VSS_17") (pintype "power_in"))
      (node (ref "U8") (pin "18") (pinfunction "VSS_18") (pintype "power_in"))
      (node (ref "U8") (pin "25") (pinfunction "EP_25") (pintype "power_in"))
      (node (ref "U9") (pin "4") (pinfunction "-VS_4") (pintype "power_in"))
      (node (ref "U9") (pin "9") (pinfunction "EP_9") (pintype "passive"))
    )
    (net (code "5") (name "/AVREF") (class "Default")
      (node (ref "C27") (pin "1") (pinfunction "1_1") (pintype "passive"))
      (node (ref "L4") (pin "2") (pinfunction "2_2") (pintype "passive"))
      (node (ref "U10") (pin "75") (pinfunction "ADVREF_75") (pintype "power_in"))
    )
    (net (code "6") (name "/CLR1") (class "Default")
      (node (ref "U10") (pin "136") (pinfunction "PC25_136") (pintype "passive"))
    )
    (net (code "7") (name "/CLR1*") (class "Default")
      (node (ref "R48") (pin "1") (pinfunction "1_1") (pintype "passive"))
      (node (ref "TP9") (pin "TP") (pinfunction "TP_TP") (pintype "passive"))
      (node (ref "U10") (pin "15") (pinfunction "PD2_15") (pintype "passive"))
      (node (ref "U5") (pin "4") (pinfunction "VIB_4") (pintype "input"))
    )
    (net (code "8") (name "/CLR2") (class "Default")
      (node (ref "U10") (pin "123") (pinfunction "PB8_123") (pintype "passive"))
    )
    (net (code "9") (name "/CLR2*") (class "Default")
      (node (ref "R9") (pin "1") (pinfunction "1_1") (pintype "passive"))
      (node (ref "TP13") (pin "TP") (pinfunction "TP_TP") (pintype "passive"))
      (node (ref "U10") (pin "19") (pinfunction "PD6_19") (pintype "passive"))
      (node (ref "U11") (pin "4") (pinfunction "VIB_4") (pintype "input"))
    )
    (net (code "10") (name "/CLR3") (class "Default")
      (node (ref "U10") (pin "64") (pinfunction "PC6_64") (pintype "passive"))
    )
    (net (code "11") (name "/CLR4") (class "Default")
      (node (ref "U10") (pin "92") (pinfunction "PB21_92") (pintype "passive"))
    )
    (net (code "12") (name "/CLR5") (class "Default")
      (node (ref "U10") (pin "98") (pinfunction "PC16_98") (pintype "passive"))
    )
    (net (code "13") (name "/CLR6") (class "Default")
      (node (ref "U10") (pin "114") (pinfunction "PB1_114") (pintype "passive"))
    )
    (net (code "14") (name "/D+") (class "Default")
      (node (ref "R11") (pin "1") (pinfunction "1_1") (pintype "passive"))
      (node (ref "R45") (pin "1") (pinfunction "1_1") (pintype "passive"))
      (node (ref "U10") (pin "37") (pinfunction "DHSDP_37") (pintype "passive"))
      (node (ref "Z1") (pin "1") (pinfunction "1_1") (pintype "passive"))
    )
    (net (code "15") (name "/D-") (class "Default")
      (node (ref "R46") (pin "1") (pinfunction "1_1") (pintype "passive"))
      (node (ref "R8") (pin "1") (pinfunction "1_1") (pintype "passive"))
      (node (ref "U10") (pin "38") (pinfunction "DHSDM_38") (pintype "passive"))
      (node (ref "Z2") (pin "1") (pinfunction "1_1") (pintype "passive"))
    )
    (net (code "16") (name "/DAC1 OUT") (class "Default")
      (node (ref "C5") (pin "1") (pinfunction "1_1") (pintype "passive"))
      (node (ref "TP1") (pin "TP") (pinfunction "TP_TP") (pintype "passive"))
      (node (ref "U3") (pin "20") (pinfunction "RFB_20") (pintype "input"))
      (node (ref "U4") (pin "6") (pinfunction "VOUT_6") (pintype "output"))
    )
    (net (code "17") (name "/DAC1_CS1") (class "Default")
      (node (ref "U10") (pin "78") (pinfunction "PA16_78") (pintype "passive"))
      (node (ref "U2") (pin "7") (pinfunction "VE1_7") (pintype "input"))
    )
    (net (code "18") (name "/DAC1_CS2") (class "Default")
      (node (ref "U10") (pin "79") (pinfunction "PA24_79") (pintype "passive"))
      (node (ref "U5") (pin "7") (pinfunction "VE1_7") (pintype "input"))
    )
    (net (code "19") (name "/DAC2 OUT") (class "Default")
      (node (ref "C57") (pin "1") (pinfunction "1_1") (pintype "passive"))
      (node (ref "TP15") (pin "TP") (pinfunction "TP_TP") (pintype "passive"))
      (node (ref "U8") (pin "20") (pinfunction "RFB_20") (pintype "input"))
      (node (ref "U9") (pin "6") (pinfunction "VOUT_6") (pintype "output"))
    )
    (net (code "20") (name "/DAC2_CS1") (class "Default")
      (node (ref "U10") (pin "70") (pinfunction "PA18_70") (pintype "passive"))
      (node (ref "U7") (pin "7") (pinfunction "VE1_7") (pintype "input"))
    )
    (net (code "21") (name "/DAC2_CS2") (class "Default")
      (node (ref "U10") (pin "71") (pinfunction "PA19_71") (pintype "passive"))
      (node (ref "U11") (pin "7") (pinfunction "VE1_7") (pintype "input"))
    )
    (net (code "22") (name "/DIR1") (class "Default")
      (node (ref "U10") (pin "135") (pinfunction "PC24_135") (pintype "passive"))
    )
    (net (code "23") (name "/DIR2") (class "Default")
      (node (ref "U10") (pin "122") (pinfunction "PB7_122") (pintype "passive"))
    )
    (net (code "24") (name "/DIR3") (class "Default")
      (node (ref "U10") (pin "63") (pinfunction "PC5_63") (pintype "passive"))
    )
    (net (code "25") (name "/DIR4") (class "Default")
      (node (ref "U10") (pin "91") (pinfunction "PB20_91") (pintype "passive"))
    )
    (net (code "26") (name "/DIR5") (class "Default")
      (node (ref "U10") (pin "97") (pinfunction "PC15_97") (pintype "passive"))
    )
    (net (code "27") (name "/DIR6") (class "Default")
      (node (ref "U10") (pin "115") (pinfunction "PB2_115") (pintype "passive"))
    )
    (net (code "28") (name "/ENC_CS") (class "Default")
      (node (ref "R25") (pin "2") (pinfunction "2_2") (pintype "passive"))
      (node (ref "U10") (pin "141") (pinfunction "PB22_141") (pintype "passive"))
      (node (ref "U6") (pin "9") (pinfunction "~{CS}_9") (pintype "input"))
    )
    (net (code "29") (name "/ERASE_S") (class "Default")
      (node (ref "ERASE1") (pin "P$1") (pinfunction "P$4_P$1") (pintype "passive"))
      (node (ref "U10") (pin "130") (pinfunction "PC0_130") (pintype "passive"))
    )
    (net (code "30") (name "/ERR1") (class "Default")
      (node (ref "U10") (pin "138") (pinfunction "PC27_138") (pintype "passive"))
    )
    (net (code "31") (name "/ERR2") (class "Default")
      (node (ref "U10") (pin "128") (pinfunction "PB10_128") (pintype "passive"))
    )
    (net (code "32") (name "/ERR3") (class "Default")
      (node (ref "U10") (pin "66") (pinfunction "PC8_66") (pintype "passive"))
    )
    (net (code "33") (name "/ERR4") (class "Default")
      (node (ref "U10") (pin "94") (pinfunction "PC12_94") (pintype "passive"))
    )
    (net (code "34") (name "/ERR5") (class "Default")
      (node (ref "U10") (pin "100") (pinfunction "PC18_100") (pintype "passive"))
    )
    (net (code "35") (name "/ERR6") (class "Default")
      (node (ref "U10") (pin "119") (pinfunction "PB4_119") (pintype "passive"))
    )
    (net (code "36") (name "/ETH_CLK") (class "Default")
      (node (ref "U10") (pin "107") (pinfunction "PA21_107") (pintype "passive"))
      (node (ref "U6") (pin "23") (pinfunction "OSC1_23") (pintype "input"))
    )
    (net (code "37") (name "/ETH_RESET") (class "Default")
      (node (ref "R27") (pin "1") (pinfunction "1_1") (pintype "passive"))
      (node (ref "U10") (pin "140") (pinfunction "PB14_140") (pintype "passive"))
      (node (ref "U6") (pin "10") (pinfunction "~{RESET}_10") (pintype "input"))
    )
    (net (code "38") (name "/HOLDCUR2") (class "Default")
      (node (ref "U10") (pin "129") (pinfunction "PB11_129") (pintype "passive"))
    )
    (net (code "39") (name "/HOLDCUR3") (class "Default")
      (node (ref "U10") (pin "67") (pinfunction "PC9_67") (pintype "passive"))
    )
    (net (code "40") (name "/HOLDCUR4") (class "Default")
      (node (ref "U10") (pin "95") (pinfunction "PC13_95") (pintype "passive"))
    )
    (net (code "41") (name "/HOLDCUR5") (class "Default")
      (node (ref "U10") (pin "101") (pinfunction "PC19_101") (pintype "passive"))
    )
    (net (code "42") (name "/HOLDCUR6") (class "Default")
      (node (ref "U10") (pin "120") (pinfunction "PB5_120") (pintype "passive"))
    )
    (net (code "43") (name "/INT") (class "Default")
      (node (ref "R36") (pin "1") (pinfunction "1_1") (pintype "passive"))
      (node (ref "U10") (pin "139") (pinfunction "PC28_139") (pintype "passive"))
      (node (ref "U6") (pin "4") (pinfunction "~{INT}_4") (pintype "output"))
    )
    (net (code "44") (name "/LDAC1*") (class "Default")
      (node (ref "R49") (pin "1") (pinfunction "1_1") (pintype "passive"))
      (node (ref "TP8") (pin "TP") (pinfunction "TP_TP") (pintype "passive"))
      (node (ref "U10") (pin "14") (pinfunction "PD1_14") (pintype "passive"))
      (node (ref "U5") (pin "5") (pinfunction "VIC_5") (pintype "input"))
    )
    (net (code "45") (name "/LDAC2*") (class "Default")
      (node (ref "R12") (pin "1") (pinfunction "1_1") (pintype "passive"))
      (node (ref "TP12") (pin "TP") (pinfunction "TP_TP") (pintype "passive"))
      (node (ref "U10") (pin "18") (pinfunction "PD5_18") (pintype "passive"))
      (node (ref "U11") (pin "5") (pinfunction "VIC_5") (pintype "input"))
    )
    (net (code "46") (name "/LEDA") (class "Default")
      (node (ref "R26") (pin "2") (pinfunction "2_2") (pintype "passive"))
      (node (ref "U6") (pin "27") (pinfunction "LEDA_27") (pintype "output"))
    )
    (net (code "47") (name "/LEDB") (class "Default")
      (node (ref "R28") (pin "2") (pinfunction "2_2") (pintype "passive"))
      (node (ref "U6") (pin "26") (pinfunction "LEDB_26") (pintype "output"))
    )
    (net (code "48") (name "/LVDT1_CS") (class "Default")
      (node (ref "U10") (pin "88") (pinfunction "PB17_88") (pintype "passive"))
    )
    (net (code "49") (name "/LVDT1_OE1") (class "Default")
      (node (ref "U10") (pin "72") (pinfunction "PA20_72") (pintype "passive"))
    )
    (net (code "50") (name "/MASTER-RESET") (class "Default")
      (node (ref "C6") (pin "2") (pinfunction "2_2") (pintype "passive"))
      (node (ref "CON1") (pin "5") (pinfunction "5_5") (pintype "passive"))
      (node (ref "CON2") (pin "6") (pinfunction "6_6") (pintype "passive"))
      (node (ref "R5") (pin "1") (pinfunction "1_1") (pintype "passive"))
      (node (ref "RESET1") (pin "P$2") (pinfunction "P$5_P$2") (pintype "passive"))
      (node (ref "U10") (pin "47") (pinfunction "NRSTB_47") (pintype "passive"))
    )
    (net (code "51") (name "/MISO") (class "Default")
      (node (ref "CON1") (pin "1") (pinfunction "1_1") (pintype "passive"))
      (node (ref "R29") (pin "1") (pinfunction "1_1") (pintype "passive"))
      (node (ref "TP4") (pin "TP") (pinfunction "TP_TP") (pintype "passive"))
      (node (ref "U10") (pin "108") (pinfunction "PA25_108") (pintype "passive"))
      (node (ref "U2") (pin "6") (pinfunction "VOD_6") (pintype "tri_state"))
      (node (ref "U6") (pin "6") (pinfunction "SO_6") (pintype "output"))
      (node (ref "U7") (pin "6") (pinfunction "VOD_6") (pintype "tri_state"))
    )
    (net (code "52") (name "/MOSI") (class "Default")
      (node (ref "CON1") (pin "4") (pinfunction "4_4") (pintype "passive"))
      (node (ref "TP5") (pin "TP") (pinfunction "TP_TP") (pintype "passive"))
      (node (ref "U10") (pin "109") (pinfunction "PA26_109") (pintype "passive"))
      (node (ref "U2") (pin "3") (pinfunction "VIA_3") (pintype "input"))
      (node (ref "U6") (pin "7") (pinfunction "SI_7") (pintype "input"))
      (node (ref "U7") (pin "3") (pinfunction "VIA_3") (pintype "input"))
    )
    (net (code "53") (name "/NXT1") (class "Default")
      (node (ref "U10") (pin "134") (pinfunction "PC23_134") (pintype "passive"))
    )
    (net (code "54") (name "/NXT2") (class "Default")
      (node (ref "U10") (pin "121") (pinfunction "PB6_121") (pintype "passive"))
    )
    (net (code "55") (name "/NXT3") (class "Default")
      (node (ref "U10") (pin "60") (pinfunction "PC3_60") (pintype "passive"))
    )
    (net (code "56") (name "/NXT4") (class "Default")
      (node (ref "U10") (pin "90") (pinfunction "PB19_90") (pintype "passive"))
    )
    (net (code "57") (name "/NXT5") (class "Default")
      (node (ref "U10") (pin "96") (pinfunction "PC14_96") (pintype "passive"))
    )
    (net (code "58") (name "/NXT6") (class "Default")
      (node (ref "U10") (pin "113") (pinfunction "PB0_113") (pintype "passive"))
    )
    (net (code "59") (name "/RELAY_CTRL_ISO1") (class "Default")
      (node (ref "U10") (pin "76") (pinfunction "PB15_76") (pintype "passive"))
    )
    (net (code "60") (name "/RELAY_CTRL_ISO2") (class "Default")
      (node (ref "U10") (pin "77") (pinfunction "PB16_77") (pintype "passive"))
    )
    (net (code "61") (name "/RESET1*") (class "Default")
      (node (ref "R47") (pin "1") (pinfunction "1_1") (pintype "passive"))
      (node (ref "TP10") (pin "TP") (pinfunction "TP_TP") (pintype "passive"))
      (node (ref "U10") (pin "16") (pinfunction "PD3_16") (pintype "passive"))
      (node (ref "U5") (pin "3") (pinfunction "VIA_3") (pintype "input"))
    )
    (net (code "62") (name "/RESET2*") (class "Default")
      (node (ref "R14") (pin "1") (pinfunction "1_1") (pintype "passive"))
      (node (ref "TP14") (pin "TP") (pinfunction "TP_TP") (pintype "passive"))
      (node (ref "U10") (pin "20") (pinfunction "PD7_20") (pintype "passive"))
      (node (ref "U11") (pin "3") (pinfunction "VIA_3") (pintype "input"))
    )
    (net (code "63") (name "/RX0") (class "Default")
      (node (ref "TP2") (pin "TP") (pinfunction "TP_TP") (pintype "passive"))
    )
    (net (code "64") (name "/SCLK") (class "Default")
      (node (ref "CON1") (pin "3") (pinfunction "3_3") (pintype "passive"))
      (node (ref "TP6") (pin "TP") (pinfunction "TP_TP") (pintype "passive"))
      (node (ref "U10") (pin "110") (pinfunction "PA27_110") (pintype "passive"))
      (node (ref "U2") (pin "4") (pinfunction "VIB_4") (pintype "input"))
      (node (ref "U6") (pin "8") (pinfunction "SCK_8") (pintype "input"))
      (node (ref "U7") (pin "4") (pinfunction "VIB_4") (pintype "input"))
    )
    (net (code "65") (name "/SLA_FILT1") (class "Default")
      (node (ref "U10") (pin "85") (pinfunction "PA2_85") (pintype "passive"))
    )
    (net (code "66") (name "/SLA_FILT2") (class "Default")
      (node (ref "U10") (pin "84") (pinfunction "PA3_84") (pintype "passive"))
    )
    (net (code "67") (name "/SLA_FILT3") (class "Default")
      (node (ref "U10") (pin "83") (pinfunction "PA4_83") (pintype "passive"))
    )
    (net (code "68") (name "/SLA_FILT4") (class "Default")
      (node (ref "U10") (pin "82") (pinfunction "PA6_82") (pintype "passive"))
    )
    (net (code "69") (name "/SLA_FILT5") (class "Default")
      (node (ref "U10") (pin "81") (pinfunction "PA22_81") (pintype "passive"))
    )
    (net (code "70") (name "/SLA_FILT6") (class "Default")
      (node (ref "U10") (pin "80") (pinfunction "PA23_80") (pintype "passive"))
    )
    (net (code "71") (name "/STP1CS") (class "Default")
      (node (ref "U10") (pin "133") (pinfunction "PC22_133") (pintype "passive"))
    )
    (net (code "72") (name "/STP2CS") (class "Default")
      (node (ref "U10") (pin "131") (pinfunction "PC20_131") (pintype "passive"))
    )
    (net (code "73") (name "/STP3CS") (class "Default")
      (node (ref "U10") (pin "59") (pinfunction "PC2_59") (pintype "passive"))
    )
    (net (code "74") (name "/STP4CS") (class "Default")
      (node (ref "U10") (pin "89") (pinfunction "PB18_89") (pintype "passive"))
    )
    (net (code "75") (name "/STP5CS") (class "Default")
      (node (ref "U10") (pin "102") (pinfunction "PC29_102") (pintype "passive"))
    )
    (net (code "76") (name "/STP6CS") (class "Default")
      (node (ref "U10") (pin "112") (pinfunction "PA29_112") (pintype "passive"))
    )
    (net (code "77") (name "/SYNC1*") (class "Default")
      (node (ref "R50") (pin "1") (pinfunction "1_1") (pintype "passive"))
      (node (ref "TP7") (pin "TP") (pinfunction "TP_TP") (pintype "passive"))
      (node (ref "U10") (pin "13") (pinfunction "PD0_13") (pintype "passive"))
      (node (ref "U2") (pin "5") (pinfunction "VIC_5") (pintype "input"))
    )
    (net (code "78") (name "/SYNC2*") (class "Default")
      (node (ref "R10") (pin "1") (pinfunction "1_1") (pintype "passive"))
      (node (ref "TP11") (pin "TP") (pinfunction "TP_TP") (pintype "passive"))
      (node (ref "U10") (pin "17") (pinfunction "PD4_17") (pintype "passive"))
      (node (ref "U7") (pin "5") (pinfunction "VIC_5") (pintype "input"))
    )
    (net (code "79") (name "/TCK") (class "Default")
      (node (ref "CON2") (pin "1") (pinfunction "1_1") (pintype "passive"))
      (node (ref "U10") (pin "28") (pinfunction "PB28_28") (pintype "passive"))
    )
    (net (code "80") (name "/TDI") (class "Default")
      (node (ref "CON2") (pin "9") (pinfunction "9_9") (pintype "passive"))
      (node (ref "U10") (pin "29") (pinfunction "PB29_29") (pintype "passive"))
    )
    (net (code "81") (name "/TDO") (class "Default")
      (node (ref "CON2") (pin "3") (pinfunction "3_3") (pintype "passive"))
      (node (ref "U10") (pin "30") (pinfunction "PB30_30") (pintype "passive"))
    )
    (net (code "82") (name "/TMS") (class "Default")
      (node (ref "CON2") (pin "5") (pinfunction "5_5") (pintype "passive"))
      (node (ref "U10") (pin "31") (pinfunction "PB31_31") (pintype "passive"))
    )
    (net (code "83") (name "/TX0") (class "Default")
      (node (ref "TP3") (pin "TP") (pinfunction "TP_TP") (pintype "passive"))
    )
    (net (code "84") (name "/USB_D+") (class "Default")
      (node (ref "R45") (pin "2") (pinfunction "2_2") (pintype "passive"))
      (node (ref "X1") (pin "3") (pinfunction "D+_3") (pintype "passive"))
    )
    (net (code "85") (name "/USB_D-") (class "Default")
      (node (ref "R46") (pin "2") (pinfunction "2_2") (pintype "passive"))
      (node (ref "X1") (pin "2") (pinfunction "D-_2") (pintype "passive"))
    )
    (net (code "86") (name "/USB_VCC") (class "Default")
      (node (ref "C3") (pin "2") (pinfunction "2_2") (pintype "passive"))
      (node (ref "C4") (pin "1") (pinfunction "1_1") (pintype "passive"))
      (node (ref "U10") (pin "39") (pinfunction "VBUS_39") (pintype "power_in"))
      (node (ref "X1") (pin "1") (pinfunction "VBUS_1") (pintype "power_in"))
    )
    (net (code "87") (name "/VBG") (class "Default")
      (node (ref "C50") (pin "1") (pinfunction "1_1") (pintype "passive"))
      (node (ref "R13") (pin "2") (pinfunction "2_2") (pintype "passive"))
      (node (ref "U10") (pin "40") (pinfunction "VBG_40") (pintype "passive"))
    )
    (net (code "88") (name "/VDDANA") (class "Default")
      (node (ref "C24") (pin "1") (pinfunction "1_1") (pintype "passive"))
      (node (ref "C25") (pin "1") (pinfunction "1_1") (pintype "passive"))
      (node (ref "L2") (pin "2") (pinfunction "2_2") (pintype "passive"))
      (node (ref "U10") (pin "73") (pinfunction "VDDANA_73") (pintype "power_in"))
    )
    (net (code "89") (name "/VDDOUT") (class "Default")
      (node (ref "C37") (pin "1") (pinfunction "1_1") (pintype "passive"))
      (node (ref "C38") (pin "1") (pinfunction "1_1") (pintype "passive"))
      (node (ref "C39") (pin "1") (pinfunction "1_1") (pintype "passive"))
      (node (ref "C40") (pin "1") (pinfunction "1_1") (pintype "passive"))
      (node (ref "C41") (pin "1") (pinfunction "1_1") (pintype "passive"))
      (node (ref "C42") (pin "1") (pinfunction "1_1") (pintype "passive"))
      (node (ref "C43") (pin "1") (pinfunction "1_1") (pintype "passive"))
      (node (ref "L5") (pin "1") (pinfunction "1_1") (pintype "passive"))
      (node (ref "U10") (pin "10") (pinfunction "VDDCORE1_10") (pintype "passive"))
      (node (ref "U10") (pin "104") (pinfunction "VDDCORE4_104") (pintype "passive"))
      (node (ref "U10") (pin "124") (pinfunction "VDDCORE5_124") (pintype "passive"))
      (node (ref "U10") (pin "45") (pinfunction "VDDCORE2_45") (pintype "passive"))
      (node (ref "U10") (pin "56") (pinfunction "VDDOUT_56") (pintype "output"))
      (node (ref "U10") (pin "61") (pinfunction "VDDCORE3_61") (pintype "passive"))
    )
    (net (code "90") (name "/VDDOUTMI") (class "Default")
      (node (ref "C22") (pin "1") (pinfunction "1_1") (pintype "passive"))
      (node (ref "C23") (pin "1") (pinfunction "1_1") (pintype "passive"))
      (node (ref "L3") (pin "2") (pinfunction "2_2") (pintype "passive"))
      (node (ref "U10") (pin "41") (pinfunction "VDDUTMI_41") (pintype "passive"))
    )
    (net (code "91") (name "/VDDPLL") (class "Default")
      (node (ref "C29") (pin "1") (pinfunction "1_1") (pintype "passive"))
      (node (ref "C30") (pin "1") (pinfunction "1_1") (pintype "passive"))
      (node (ref "L5") (pin "2") (pinfunction "2_2") (pintype "passive"))
      (node (ref "U10") (pin "34") (pinfunction "VDDPLL_34") (pintype "passive"))
    )
    (net (code "92") (name "/VN10") (class "Default")
      (node (ref "C58") (pin "2") (pinfunction "2_2") (pintype "passive"))
      (node (ref "U3") (pin "16") (pinfunction "VREFN_16") (pintype "input"))
      (node (ref "U8") (pin "16") (pinfunction "VREFN_16") (pintype "input"))
    )
    (net (code "93") (name "/VP10") (class "Default")
      (node (ref "C59") (pin "2") (pinfunction "2_2") (pintype "passive"))
      (node (ref "U3") (pin "2") (pinfunction "VREFP_2") (pintype "input"))
      (node (ref "U8") (pin "2") (pinfunction "VREFP_2") (pintype "input"))
    )
    (net (code "94") (name "/WD1") (class "Default")
      (node (ref "U10") (pin "137") (pinfunction "PC26_137") (pintype "passive"))
    )
    (net (code "95") (name "/WD2") (class "Default")
      (node (ref "U10") (pin "127") (pinfunction "PB9_127") (pintype "passive"))
    )
    (net (code "96") (name "/WD3") (class "Default")
      (node (ref "U10") (pin "65") (pinfunction "PC7_65") (pintype "passive"))
    )
    (net (code "97") (name "/WD4") (class "Default")
      (node (ref "U10") (pin "93") (pinfunction "PC11_93") (pintype "passive"))
    )
    (net (code "98") (name "/WD5") (class "Default")
      (node (ref "U10") (pin "99") (pinfunction "PC17_99") (pintype "passive"))
    )
    (net (code "99") (name "/WD6") (class "Default")
      (node (ref "U10") (pin "118") (pinfunction "PB3_118") (pintype "passive"))
    )
    (net (code "100") (name "/XIN") (class "Default")
      (node (ref "C45") (pin "1") (pinfunction "1_1") (pintype "passive"))
      (node (ref "U10") (pin "36") (pinfunction "XIN_36") (pintype "passive"))
      (node (ref "Y2") (pin "1") (pinfunction "C1_1") (pintype "passive"))
    )
    (net (code "101") (name "/XIN32") (class "Default")
      (node (ref "C49") (pin "1") (pinfunction "1_1") (pintype "passive"))
      (node (ref "U10") (pin "48") (pinfunction "XIN32_48") (pintype "output"))
      (node (ref "Y1") (pin "P$2") (pinfunction "2_P$2") (pintype "passive"))
    )
    (net (code "102") (name "/XOUT") (class "Default")
      (node (ref "C44") (pin "1") (pinfunction "1_1") (pintype "passive"))
      (node (ref "U10") (pin "35") (pinfunction "XOUT_35") (pintype "output"))
      (node (ref "Y2") (pin "3") (pinfunction "C2_3") (pintype "passive"))
    )
    (net (code "103") (name "/XOUT32") (class "Default")
      (node (ref "C48") (pin "1") (pinfunction "1_1") (pintype "passive"))
      (node (ref "U10") (pin "49") (pinfunction "XOUT32_49") (pintype "output"))
      (node (ref "Y1") (pin "P$1") (pinfunction "1_P$1") (pintype "passive"))
    )
    (net (code "104") (name "AGND") (class "Default")
      (node (ref "C1") (pin "1") (pinfunction "1_1") (pintype "passive"))
      (node (ref "C10") (pin "1") (pinfunction "1_1") (pintype "passive"))
      (node (ref "C11") (pin "2") (pinfunction "2_2") (pintype "passive"))
      (node (ref "C13") (pin "1") (pinfunction "1_1") (pintype "passive"))
      (node (ref "C14") (pin "2") (pinfunction "2_2") (pintype "passive"))
      (node (ref "C2") (pin "2") (pinfunction "2_2") (pintype "passive"))
      (node (ref "C32") (pin "1") (pinfunction "1_1") (pintype "passive"))
      (node (ref "C33") (pin "2") (pinfunction "2_2") (pintype "passive"))
      (node (ref "C46") (pin "2") (pinfunction "2_2") (pintype "passive"))
      (node (ref "C55") (pin "1") (pinfunction "1_1") (pintype "passive"))
      (node (ref "C56") (pin "2") (pinfunction "2_2") (pintype "passive"))
      (node (ref "C58") (pin "1") (pinfunction "1_1") (pintype "passive"))
      (node (ref "C59") (pin "1") (pinfunction "1_1") (pintype "passive"))
      (node (ref "C60") (pin "2") (pinfunction "2_2") (pintype "passive"))
      (node (ref "C61") (pin "1") (pinfunction "1_1") (pintype "passive"))
      (node (ref "C62") (pin "2") (pinfunction "2_2") (pintype "passive"))
      (node (ref "C63") (pin "1") (pinfunction "1_1") (pintype "passive"))
      (node (ref "C65") (pin "2") (pinfunction "2_2") (pintype "passive"))
      (node (ref "C67") (pin "1") (pinfunction "1_1") (pintype "passive"))
      (node (ref "C68") (pin "2") (pinfunction "2_2") (pintype "passive"))
      (node (ref "C7") (pin "2") (pinfunction "2_2") (pintype "passive"))
      (node (ref "C70") (pin "1") (pinfunction "1_1") (pintype "passive"))
      (node (ref "C71") (pin "2") (pinfunction "2_2") (pintype "passive"))
      (node (ref "C72") (pin "2") (pinfunction "2_2") (pintype "passive"))
      (node (ref "C8") (pin "1") (pinfunction "1_1") (pintype "passive"))
      (node (ref "C9") (pin "2") (pinfunction "2_2") (pintype "passive"))
      (node (ref "U11") (pin "15") (pinfunction "GND2_15") (pintype "power_in"))
      (node (ref "U11") (pin "9") (pinfunction "GND2_9") (pintype "power_in"))
      (node (ref "U2") (pin "15") (pinfunction "GND2_15") (pintype "power_in"))
      (node (ref "U2") (pin "9") (pinfunction "GND2_9") (pintype "power_in"))
      (node (ref "U3") (pin "15") (pinfunction "DGND_15") (pintype "power_in"))
      (node (ref "U3") (pin "19") (pinfunction "AGND_19") (pintype "power_in"))
      (node (ref "U5") (pin "15") (pinfunction "GND2_15") (pintype "power_in"))
      (node (ref "U5") (pin "9") (pinfunction "GND2_9") (pintype "power_in"))
      (node (ref "U7") (pin "15") (pinfunction "GND2_15") (pintype "power_in"))
      (node (ref "U7") (pin "9") (pinfunction "GND2_9") (pintype "power_in"))
      (node (ref "U8") (pin "15") (pinfunction "DGND_15") (pintype "power_in"))
      (node (ref "U8") (pin "19") (pinfunction "AGND_19") (pintype "power_in"))
    )
    (net (code "105") (name "DGND") (class "Default")
      (node (ref "C12") (pin "2") (pinfunction "2_2") (pintype "passive"))
      (node (ref "C15") (pin "2") (pinfunction "2_2") (pintype "passive"))
      (node (ref "C16") (pin "2") (pinfunction "2_2") (pintype "passive"))
      (node (ref "C17") (pin "2") (pinfunction "2_2") (pintype "passive"))
      (node (ref "C18") (pin "2") (pinfunction "2_2") (pintype "passive"))
      (node (ref "C19") (pin "2") (pinfunction "2_2") (pintype "passive"))
      (node (ref "C20") (pin "2") (pinfunction "2_2") (pintype "passive"))
      (node (ref "C21") (pin "2") (pinfunction "2_2") (pintype "passive"))
      (node (ref "C22") (pin "2") (pinfunction "2_2") (pintype "passive"))
      (node (ref "C23") (pin "2") (pinfunction "2_2") (pintype "passive"))
      (node (ref "C24") (pin "2") (pinfunction "2_2") (pintype "passive"))
      (node (ref "C25") (pin "2") (pinfunction "2_2") (pintype "passive"))
      (node (ref "C26") (pin "2") (pinfunction "2_2") (pintype "passive"))
      (node (ref "C27") (pin "2") (pinfunction "2_2") (pintype "passive"))
      (node (ref "C29") (pin "2") (pinfunction "2_2") (pintype "passive"))
      (node (ref "C3") (pin "1") (pinfunction "1_1") (pintype "passive"))
      (node (ref "C30") (pin "2") (pinfunction "2_2") (pintype "passive"))
      (node (ref "C37") (pin "2") (pinfunction "2_2") (pintype "passive"))
      (node (ref "C38") (pin "2") (pinfunction "2_2") (pintype "passive"))
      (node (ref "C39") (pin "2") (pinfunction "2_2") (pintype "passive"))
      (node (ref "C4") (pin "2") (pinfunction "2_2") (pintype "passive"))
      (node (ref "C40") (pin "2") (pinfunction "2_2") (pintype "passive"))
      (node (ref "C41") (pin "2") (pinfunction "2_2") (pintype "passive"))
      (node (ref "C42") (pin "2") (pinfunction "2_2") (pintype "passive"))
      (node (ref "C43") (pin "2") (pinfunction "2_2") (pintype "passive"))
      (node (ref "C44") (pin "2") (pinfunction "2_2") (pintype "passive"))
      (node (ref "C45") (pin "2") (pinfunction "2_2") (pintype "passive"))
      (node (ref "C47") (pin "2") (pinfunction "2_2") (pintype "passive"))
      (node (ref "C48") (pin "2") (pinfunction "2_2") (pintype "passive"))
      (node (ref "C49") (pin "2") (pinfunction "2_2") (pintype "passive"))
      (node (ref "C50") (pin "2") (pinfunction "2_2") (pintype "passive"))
      (node (ref "C51") (pin "2") (pinfunction "2_2") (pintype "passive"))
      (node (ref "C52") (pin "1") (pinfunction "1_1") (pintype "passive"))
      (node (ref "C53") (pin "2") (pinfunction "2_2") (pintype "passive"))
      (node (ref "C54") (pin "2") (pinfunction "2_2") (pintype "passive"))
      (node (ref "C64") (pin "1") (pinfunction "1_1") (pintype "passive"))
      (node (ref "C66") (pin "2") (pinfunction "2_2") (pintype "passive"))
      (node (ref "C73") (pin "2") (pinfunction "2_2") (pintype "passive"))
      (node (ref "CON1") (pin "6") (pinfunction "6_6") (pintype "passive"))
      (node (ref "CON2") (pin "10") (pinfunction "10_10") (pintype "passive"))
      (node (ref "CON2") (pin "2") (pinfunction "2_2") (pintype "passive"))
      (node (ref "HEARTBEAT1") (pin "C") (pinfunction "C_C") (pintype "passive"))
      (node (ref "J1") (pin "10") (pinfunction "10_10") (pintype "passive"))
      (node (ref "J1") (pin "11") (pinfunction "11_11") (pintype "passive"))
      (node (ref "J1") (pin "S1") (pinfunction "S1_S1") (pintype "passive"))
      (node (ref "J1") (pin "S2") (pinfunction "S2_S2") (pintype "passive"))
      (node (ref "R13") (pin "1") (pinfunction "1_1") (pintype "passive"))
      (node (ref "R25") (pin "1") (pinfunction "1_1") (pintype "passive"))
      (node (ref "R30") (pin "1") (pinfunction "1_1") (pintype "passive"))
      (node (ref "RESET1") (pin "P$1") (pinfunction "P$4_P$1") (pintype "passive"))
      (node (ref "U10") (pin "106") (pinfunction "GND3_106") (pintype "power_in"))
      (node (ref "U10") (pin "12") (pinfunction "GND1_12") (pintype "power_in"))
      (node (ref "U10") (pin "126") (pinfunction "GND4_126") (pintype "power_in"))
      (node (ref "U10") (pin "33") (pinfunction "GNDPLL_33") (pintype "power_in"))
      (node (ref "U10") (pin "44") (pinfunction "GNDUTMI_44") (pintype "power_in"))
      (node (ref "U10") (pin "46") (pinfunction "JTAGSEL_46") (pintype "passive"))
      (node (ref "U10") (pin "54") (pinfunction "GNDBU_54") (pintype "power_in"))
      (node (ref "U10") (pin "58") (pinfunction "GND2_58") (pintype "power_in"))
      (node (ref "U10") (pin "74") (pinfunction "GNDANA_74") (pintype "power_in"))
      (node (ref "U11") (pin "2") (pinfunction "GND1_2") (pintype "power_in"))
      (node (ref "U11") (pin "8") (pinfunction "GND1_8") (pintype "power_in"))
      (node (ref "U2") (pin "2") (pinfunction "GND1_2") (pintype "power_in"))
      (node (ref "U2") (pin "8") (pinfunction "GND1_8") (pintype "power_in"))
      (node (ref "U5") (pin "2") (pinfunction "GND1_2") (pintype "power_in"))
      (node (ref "U5") (pin "8") (pinfunction "GND1_8") (pintype "power_in"))
      (node (ref "U6") (pin "11") (pinfunction "VSSRX_11") (pintype "power_in"))
      (node (ref "U6") (pin "18") (pinfunction "VSSTX_18") (pintype "power_in"))
      (node (ref "U6") (pin "2") (pinfunction "VSS_2") (pintype "power_in"))
      (node (ref "U6") (pin "21") (pinfunction "VSSPLL_21") (pintype "power_in"))
      (node (ref "U6") (pin "22") (pinfunction "VSSOSC_22") (pintype "power_in"))
      (node (ref "U7") (pin "2") (pinfunction "GND1_2") (pintype "power_in"))
      (node (ref "U7") (pin "8") (pinfunction "GND1_8") (pintype "power_in"))
      (node (ref "X1") (pin "5") (pinfunction "GND_5") (pintype "power_in"))
      (node (ref "X1") (pin "6") (pinfunction "SHLD1_6") (pintype "passive"))
      (node (ref "X1") (pin "7") (pinfunction "SHLD2_7") (pintype "passive"))
      (node (ref "X1") (pin "8") (pinfunction "SHLD3_8") (pintype "passive"))
      (node (ref "X1") (pin "9") (pinfunction "SHLD4_9") (pintype "passive"))
      (node (ref "Y2") (pin "2") (pinfunction "GND_2") (pintype "passive"))
      (node (ref "Y2") (pin "4") (pinfunction "GND_4") (pintype "passive"))
      (node (ref "Z1") (pin "2") (pinfunction "2_2") (pintype "passive"))
      (node (ref "Z2") (pin "2") (pinfunction "2_2") (pintype "passive"))
    )
    (net (code "106") (name "Eth_GND") (class "Default")
      (node (ref "C69") (pin "1") (pinfunction "1_1") (pintype "passive"))
      (node (ref "J1") (pin "8") (pinfunction "CHS_GROUND_8") (pintype "passive"))
    )
    (net (code "107") (name "Net-(C53-Pad1)") (class "Default")
      (node (ref "C53") (pin "1") (pinfunction "1_1") (pintype "passive"))
      (node (ref "R21") (pin "1") (pinfunction "1_1") (pintype "passive"))
      (node (ref "R22") (pin "1") (pinfunction "1_1") (pintype "passive"))
    )
    (net (code "108") (name "Net-(C54-Pad1)") (class "Default")
      (node (ref "C54") (pin "1") (pinfunction "1_1") (pintype "passive"))
      (node (ref "L7") (pin "2") (pinfunction "2_2") (pintype "passive"))
      (node (ref "R23") (pin "1") (pinfunction "1_1") (pintype "passive"))
      (node (ref "R24") (pin "1") (pinfunction "1_1") (pintype "passive"))
      (node (ref "T1") (pin "15") (pinfunction "CT_15") (pintype "passive"))
    )
    (net (code "109") (name "Net-(C69-Pad2)") (class "Default")
      (node (ref "C69") (pin "2") (pinfunction "2_2") (pintype "passive"))
      (node (ref "R31") (pin "2") (pinfunction "2_2") (pintype "passive"))
      (node (ref "R32") (pin "2") (pinfunction "2_2") (pintype "passive"))
      (node (ref "R33") (pin "2") (pinfunction "2_2") (pintype "passive"))
      (node (ref "R34") (pin "2") (pinfunction "2_2") (pintype "passive"))
    )
    (net (code "110") (name "Net-(HEARTBEAT1-PadA)") (class "Default")
      (node (ref "HEARTBEAT1") (pin "A") (pinfunction "A_A") (pintype "passive"))
      (node (ref "R38") (pin "1") (pinfunction "1_1") (pintype "passive"))
    )
    (net (code "111") (name "Net-(J1-Pad9)") (class "Default")
      (node (ref "J1") (pin "9") (pinfunction "9_9") (pintype "passive"))
      (node (ref "R26") (pin "1") (pinfunction "1_1") (pintype "passive"))
    )
    (net (code "112") (name "Net-(J1-Pad12)") (class "Default")
      (node (ref "J1") (pin "12") (pinfunction "12_12") (pintype "passive"))
      (node (ref "R28") (pin "1") (pinfunction "1_1") (pintype "passive"))
    )
    (net (code "113") (name "Net-(J1-RCT)") (class "Default")
      (node (ref "J1") (pin "5") (pinfunction "RCT_5") (pintype "passive"))
      (node (ref "R31") (pin "1") (pinfunction "1_1") (pintype "passive"))
    )
    (net (code "114") (name "Net-(J1-RD+)") (class "Default")
      (node (ref "J1") (pin "3") (pinfunction "RD+_3") (pintype "passive"))
      (node (ref "T1") (pin "6") (pinfunction "RD+_6") (pintype "passive"))
    )
    (net (code "115") (name "Net-(J1-RD-)") (class "Default")
      (node (ref "J1") (pin "6") (pinfunction "RD-_6") (pintype "passive"))
      (node (ref "T1") (pin "8") (pinfunction "RD-_8") (pintype "passive"))
    )
    (net (code "116") (name "Net-(J1-TCT)") (class "Default")
      (node (ref "J1") (pin "4") (pinfunction "TCT_4") (pintype "passive"))
      (node (ref "R32") (pin "1") (pinfunction "1_1") (pintype "passive"))
    )
    (net (code "117") (name "Net-(J1-TD+)") (class "Default")
      (node (ref "J1") (pin "1") (pinfunction "TD+_1") (pintype "passive"))
      (node (ref "T1") (pin "1") (pinfunction "TD+_1") (pintype "passive"))
    )
    (net (code "118") (name "Net-(J1-TD-)") (class "Default")
      (node (ref "J1") (pin "2") (pinfunction "TD-_2") (pintype "passive"))
      (node (ref "T1") (pin "3") (pinfunction "TD-_3") (pintype "passive"))
    )
    (net (code "119") (name "Net-(R33-Pad1)") (class "Default")
      (node (ref "R33") (pin "1") (pinfunction "1_1") (pintype "passive"))
      (node (ref "T1") (pin "2") (pinfunction "CT_2") (pintype "passive"))
    )
    (net (code "120") (name "Net-(R34-Pad1)") (class "Default")
      (node (ref "R34") (pin "1") (pinfunction "1_1") (pintype "passive"))
      (node (ref "T1") (pin "7") (pinfunction "CT_7") (pintype "passive"))
    )
    (net (code "121") (name "Net-(T1-RX+)") (class "Default")
      (node (ref "R21") (pin "2") (pinfunction "2_2") (pintype "passive"))
      (node (ref "T1") (pin "11") (pinfunction "RX+_11") (pintype "passive"))
      (node (ref "U6") (pin "13") (pinfunction "TPIN+_13") (pintype "input"))
    )
    (net (code "122") (name "Net-(T1-RX-)") (class "Default")
      (node (ref "R22") (pin "2") (pinfunction "2_2") (pintype "passive"))
      (node (ref "T1") (pin "9") (pinfunction "RX-_9") (pintype "passive"))
      (node (ref "U6") (pin "12") (pinfunction "TPIN-_12") (pintype "input"))
    )
    (net (code "123") (name "Net-(T1-TX+)") (class "Default")
      (node (ref "R23") (pin "2") (pinfunction "2_2") (pintype "passive"))
      (node (ref "T1") (pin "16") (pinfunction "TX+_16") (pintype "passive"))
      (node (ref "U6") (pin "17") (pinfunction "TPOUT+_17") (pintype "output"))
    )
    (net (code "124") (name "Net-(T1-TX-)") (class "Default")
      (node (ref "R24") (pin "2") (pinfunction "2_2") (pintype "passive"))
      (node (ref "T1") (pin "14") (pinfunction "TX-_14") (pintype "passive"))
      (node (ref "U6") (pin "16") (pinfunction "TPOUT-_16") (pintype "output"))
    )
    (net (code "125") (name "Net-(U2-VDD2)") (class "Default")
      (node (ref "C11") (pin "1") (pinfunction "1_1") (pintype "passive"))
      (node (ref "L1") (pin "2") (pinfunction "2_2") (pintype "passive"))
      (node (ref "U2") (pin "16") (pinfunction "VDD2_16") (pintype "power_in"))
    )
    (net (code "126") (name "Net-(U2-VID)") (class "Default")
      (node (ref "U2") (pin "11") (pinfunction "VID_11") (pintype "input"))
      (node (ref "U3") (pin "11") (pinfunction "SDO_11") (pintype "tri_state"))
    )
    (net (code "127") (name "Net-(U2-VOA)") (class "Default")
      (node (ref "U2") (pin "14") (pinfunction "VOA_14") (pintype "tri_state"))
      (node (ref "U3") (pin "12") (pinfunction "SDIN_12") (pintype "input"))
    )
    (net (code "128") (name "Net-(U2-VOB)") (class "Default")
      (node (ref "U2") (pin "13") (pinfunction "VOB_13") (pintype "tri_state"))
      (node (ref "U3") (pin "13") (pinfunction "SCLK_13") (pintype "input"))
    )
    (net (code "129") (name "Net-(U2-VOC)") (class "Default")
      (node (ref "U2") (pin "12") (pinfunction "VOC_12") (pintype "tri_state"))
      (node (ref "U3") (pin "14") (pinfunction "~{SYNC}_14") (pintype "input"))
    )
    (net (code "130") (name "Net-(U3-INV)") (class "Default")
      (node (ref "C5") (pin "2") (pinfunction "2_2") (pintype "passive"))
      (node (ref "U3") (pin "24") (pinfunction "INV_24") (pintype "passive"))
      (node (ref "U4") (pin "2") (pinfunction "-IN_2") (pintype "input"))
    )
    (net (code "131") (name "Net-(U3-VOUT)") (class "Default")
      (node (ref "U3") (pin "1") (pinfunction "VOUT_1") (pintype "tri_state"))
      (node (ref "U4") (pin "3") (pinfunction "+IN_3") (pintype "input"))
    )
    (net (code "132") (name "Net-(U3-~{CLR})") (class "Default")
      (node (ref "U3") (pin "6") (pinfunction "~{CLR}_6") (pintype "input"))
      (node (ref "U5") (pin "13") (pinfunction "VOB_13") (pintype "tri_state"))
    )
    (net (code "133") (name "Net-(U3-~{LDAC})") (class "Default")
      (node (ref "U3") (pin "7") (pinfunction "~{LDAC}_7") (pintype "input"))
      (node (ref "U5") (pin "12") (pinfunction "VOC_12") (pintype "tri_state"))
    )
    (net (code "134") (name "Net-(U3-~{RESET})") (class "Default")
      (node (ref "U3") (pin "4") (pinfunction "~{RESET}_4") (pintype "input"))
      (node (ref "U5") (pin "14") (pinfunction "VOA_14") (pintype "tri_state"))
    )
    (net (code "135") (name "Net-(U5-VDD2)") (class "Default")
      (node (ref "C46") (pin "1") (pinfunction "1_1") (pintype "passive"))
      (node (ref "L6") (pin "2") (pinfunction "2_2") (pintype "passive"))
      (node (ref "U5") (pin "16") (pinfunction "VDD2_16") (pintype "power_in"))
    )
    (net (code "136") (name "Net-(U6-RBIAS)") (class "Default")
      (node (ref "R30") (pin "2") (pinfunction "2_2") (pintype "passive"))
      (node (ref "U6") (pin "14") (pinfunction "RBIAS_14") (pintype "input"))
    )
    (net (code "137") (name "Net-(U6-VCAP)") (class "Default")
      (node (ref "C64") (pin "2") (pinfunction "2_2") (pintype "passive"))
      (node (ref "U6") (pin "1") (pinfunction "VCAP_1") (pintype "power_in"))
    )
    (net (code "138") (name "Net-(U7-VDD2)") (class "Default")
      (node (ref "C65") (pin "1") (pinfunction "1_1") (pintype "passive"))
      (node (ref "L8") (pin "2") (pinfunction "2_2") (pintype "passive"))
      (node (ref "U7") (pin "16") (pinfunction "VDD2_16") (pintype "power_in"))
    )
    (net (code "139") (name "Net-(U7-VID)") (class "Default")
      (node (ref "U7") (pin "11") (pinfunction "VID_11") (pintype "input"))
      (node (ref "U8") (pin "11") (pinfunction "SDO_11") (pintype "tri_state"))
    )
    (net (code "140") (name "Net-(U7-VOA)") (class "Default")
      (node (ref "U7") (pin "14") (pinfunction "VOA_14") (pintype "tri_state"))
      (node (ref "U8") (pin "12") (pinfunction "SDIN_12") (pintype "input"))
    )
    (net (code "141") (name "Net-(U7-VOB)") (class "Default")
      (node (ref "U7") (pin "13") (pinfunction "VOB_13") (pintype "tri_state"))
      (node (ref "U8") (pin "13") (pinfunction "SCLK_13") (pintype "input"))
    )
    (net (code "142") (name "Net-(U7-VOC)") (class "Default")
      (node (ref "U7") (pin "12") (pinfunction "VOC_12") (pintype "tri_state"))
      (node (ref "U8") (pin "14") (pinfunction "~{SYNC}_14") (pintype "input"))
    )
    (net (code "143") (name "Net-(U8-INV)") (class "Default")
      (node (ref "C57") (pin "2") (pinfunction "2_2") (pintype "passive"))
      (node (ref "U8") (pin "24") (pinfunction "INV_24") (pintype "passive"))
      (node (ref "U9") (pin "2") (pinfunction "-IN_2") (pintype "input"))
    )
    (net (code "144") (name "Net-(U8-VOUT)") (class "Default")
      (node (ref "U8") (pin "1") (pinfunction "VOUT_1") (pintype "tri_state"))
      (node (ref "U9") (pin "3") (pinfunction "+IN_3") (pintype "input"))
    )
    (net (code "145") (name "Net-(U10-DFSDM)") (class "Default")
      (node (ref "R8") (pin "2") (pinfunction "2_2") (pintype "passive"))
      (node (ref "U10") (pin "43") (pinfunction "DFSDM_43") (pintype "passive"))
    )
    (net (code "146") (name "Net-(U10-DFSDP)") (class "Default")
      (node (ref "R11") (pin "2") (pinfunction "2_2") (pintype "passive"))
      (node (ref "U10") (pin "42") (pinfunction "DFSDP_42") (pintype "passive"))
    )
    (net (code "147") (name "Net-(U10-FWUP)") (class "Default")
      (node (ref "R37") (pin "1") (pinfunction "1_1") (pintype "passive"))
      (node (ref "U10") (pin "53") (pinfunction "FWUP_53") (pintype "passive"))
    )
    (net (code "148") (name "Net-(U10-PB27)") (class "Default")
      (node (ref "R38") (pin "2") (pinfunction "2_2") (pintype "passive"))
      (node (ref "U10") (pin "68") (pinfunction "PB27_68") (pintype "passive"))
    )
    (net (code "149") (name "Net-(U11-VDD2)") (class "Default")
      (node (ref "C72") (pin "1") (pinfunction "1_1") (pintype "passive"))
      (node (ref "L9") (pin "2") (pinfunction "2_2") (pintype "passive"))
      (node (ref "U11") (pin "16") (pinfunction "VDD2_16") (pintype "power_in"))
    )
    (net (code "150") (name "Net-(U11-VOA)") (class "Default")
      (node (ref "U11") (pin "14") (pinfunction "VOA_14") (pintype "tri_state"))
      (node (ref "U8") (pin "4") (pinfunction "~{RESET}_4") (pintype "input"))
    )
    (net (code "151") (name "Net-(U11-VOB)") (class "Default")
      (node (ref "U11") (pin "13") (pinfunction "VOB_13") (pintype "tri_state"))
      (node (ref "U8") (pin "6") (pinfunction "~{CLR}_6") (pintype "input"))
    )
    (net (code "152") (name "Net-(U11-VOC)") (class "Default")
      (node (ref "U11") (pin "12") (pinfunction "VOC_12") (pintype "tri_state"))
      (node (ref "U8") (pin "7") (pinfunction "~{LDAC}_7") (pintype "input"))
    )
    (net (code "153") (name "unconnected-(C20-Pad1)") (class "Default")
      (node (ref "C20") (pin "1") (pinfunction "1_1") (pintype "passive"))
    )
    (net (code "154") (name "unconnected-(CON2-Pad8)") (class "Default")
      (node (ref "CON2") (pin "8") (pinfunction "8_8") (pintype "passive"))
    )
    (net (code "155") (name "unconnected-(J1-NC-Pad7)") (class "Default")
      (node (ref "J1") (pin "7") (pinfunction "NC_7") (pintype "passive+no_connect"))
    )
    (net (code "156") (name "unconnected-(T1-CT-Pad10)") (class "Default")
      (node (ref "T1") (pin "10") (pinfunction "CT_10") (pintype "passive+no_connect"))
    )
    (net (code "157") (name "unconnected-(T1-NC-Pad4)") (class "Default")
      (node (ref "T1") (pin "4") (pinfunction "NC_4") (pintype "passive+no_connect"))
    )
    (net (code "158") (name "unconnected-(T1-NC-Pad5)") (class "Default")
      (node (ref "T1") (pin "5") (pinfunction "NC_5") (pintype "passive+no_connect"))
    )
    (net (code "159") (name "unconnected-(T1-NC-Pad12)") (class "Default")
      (node (ref "T1") (pin "12") (pinfunction "NC_12") (pintype "passive+no_connect"))
    )
    (net (code "160") (name "unconnected-(T1-NC-Pad13)") (class "Default")
      (node (ref "T1") (pin "13") (pinfunction "NC_13") (pintype "passive+no_connect"))
    )
    (net (code "161") (name "unconnected-(U3-DNC-Pad10)") (class "Default")
      (node (ref "U3") (pin "10") (pinfunction "DNC_10") (pintype "passive+no_connect"))
    )
    (net (code "162") (name "unconnected-(U3-DNC-Pad21)") (class "Default")
      (node (ref "U3") (pin "21") (pinfunction "DNC_21") (pintype "passive+no_connect"))
    )
    (net (code "163") (name "unconnected-(U3-DNC-Pad22)") (class "Default")
      (node (ref "U3") (pin "22") (pinfunction "DNC_22") (pintype "passive+no_connect"))
    )
    (net (code "164") (name "unconnected-(U3-DNC-Pad23)") (class "Default")
      (node (ref "U3") (pin "23") (pinfunction "DNC_23") (pintype "passive+no_connect"))
    )
    (net (code "165") (name "unconnected-(U4-NC-Pad1)") (class "Default")
      (node (ref "U4") (pin "1") (pinfunction "NC_1") (pintype "passive"))
    )
    (net (code "166") (name "unconnected-(U4-NC-Pad5)") (class "Default")
      (node (ref "U4") (pin "5") (pinfunction "NC_5") (pintype "passive+no_connect"))
    )
    (net (code "167") (name "unconnected-(U4-~{PD}-Pad8)") (class "Default")
      (node (ref "U4") (pin "8") (pinfunction "~{PD}_8") (pintype "input+no_connect"))
    )
    (net (code "168") (name "unconnected-(U5-VID-Pad11)") (class "Default")
      (node (ref "U5") (pin "11") (pinfunction "VID_11") (pintype "input+no_connect"))
    )
    (net (code "169") (name "unconnected-(U5-VOD-Pad6)") (class "Default")
      (node (ref "U5") (pin "6") (pinfunction "VOD_6") (pintype "tri_state+no_connect"))
    )
    (net (code "170") (name "unconnected-(U6-CLKOUT-Pad3)") (class "Default")
      (node (ref "U6") (pin "3") (pinfunction "CLKOUT_3") (pintype "output+no_connect"))
    )
    (net (code "171") (name "unconnected-(U6-NC-Pad5)") (class "Default")
      (node (ref "U6") (pin "5") (pinfunction "NC_5") (pintype "passive+no_connect"))
    )
    (net (code "172") (name "unconnected-(U6-OSC2-Pad24)") (class "Default")
      (node (ref "U6") (pin "24") (pinfunction "OSC2_24") (pintype "output+no_connect"))
    )
    (net (code "173") (name "unconnected-(U8-DNC-Pad10)") (class "Default")
      (node (ref "U8") (pin "10") (pinfunction "DNC_10") (pintype "passive+no_connect"))
    )
    (net (code "174") (name "unconnected-(U8-DNC-Pad21)") (class "Default")
      (node (ref "U8") (pin "21") (pinfunction "DNC_21") (pintype "passive+no_connect"))
    )
    (net (code "175") (name "unconnected-(U8-DNC-Pad22)") (class "Default")
      (node (ref "U8") (pin "22") (pinfunction "DNC_22") (pintype "passive+no_connect"))
    )
    (net (code "176") (name "unconnected-(U8-DNC-Pad23)") (class "Default")
      (node (ref "U8") (pin "23") (pinfunction "DNC_23") (pintype "passive+no_connect"))
    )
    (net (code "177") (name "unconnected-(U9-NC-Pad1)") (class "Default")
      (node (ref "U9") (pin "1") (pinfunction "NC_1") (pintype "passive"))
    )
    (net (code "178") (name "unconnected-(U9-NC-Pad5)") (class "Default")
      (node (ref "U9") (pin "5") (pinfunction "NC_5") (pintype "passive+no_connect"))
    )
    (net (code "179") (name "unconnected-(U9-~{PD}-Pad8)") (class "Default")
      (node (ref "U9") (pin "8") (pinfunction "~{PD}_8") (pintype "input+no_connect"))
    )
    (net (code "180") (name "unconnected-(U10-NRST-Pad69)") (class "Default")
      (node (ref "U10") (pin "69") (pinfunction "NRST_69") (pintype "passive"))
    )
    (net (code "181") (name "unconnected-(U10-PA0-Pad23)") (class "Default")
      (node (ref "U10") (pin "23") (pinfunction "PA0_23") (pintype "passive"))
    )
    (net (code "182") (name "unconnected-(U10-PA1-Pad24)") (class "Default")
      (node (ref "U10") (pin "24") (pinfunction "PA1_24") (pintype "passive"))
    )
    (net (code "183") (name "unconnected-(U10-PA5-Pad25)") (class "Default")
      (node (ref "U10") (pin "25") (pinfunction "PA5_25") (pintype "passive"))
    )
    (net (code "184") (name "unconnected-(U10-PA7-Pad26)") (class "Default")
      (node (ref "U10") (pin "26") (pinfunction "PA7_26") (pintype "passive"))
    )
    (net (code "185") (name "unconnected-(U10-PA8-Pad27)") (class "Default")
      (node (ref "U10") (pin "27") (pinfunction "PA8_27") (pintype "passive"))
    )
    (net (code "186") (name "unconnected-(U10-PA9-Pad2)") (class "Default")
      (node (ref "U10") (pin "2") (pinfunction "PA9_2") (pintype "passive"))
    )
    (net (code "187") (name "unconnected-(U10-PA10-Pad3)") (class "Default")
      (node (ref "U10") (pin "3") (pinfunction "PA10_3") (pintype "passive"))
    )
    (net (code "188") (name "unconnected-(U10-PA11-Pad4)") (class "Default")
      (node (ref "U10") (pin "4") (pinfunction "PA11_4") (pintype "passive"))
    )
    (net (code "189") (name "unconnected-(U10-PA12-Pad5)") (class "Default")
      (node (ref "U10") (pin "5") (pinfunction "PA12_5") (pintype "passive"))
    )
    (net (code "190") (name "unconnected-(U10-PA13-Pad6)") (class "Default")
      (node (ref "U10") (pin "6") (pinfunction "PA13_6") (pintype "passive"))
    )
    (net (code "191") (name "unconnected-(U10-PA14-Pad7)") (class "Default")
      (node (ref "U10") (pin "7") (pinfunction "PA14_7") (pintype "passive"))
    )
    (net (code "192") (name "unconnected-(U10-PA15-Pad8)") (class "Default")
      (node (ref "U10") (pin "8") (pinfunction "PA15_8") (pintype "passive"))
    )
    (net (code "193") (name "unconnected-(U10-PA17-Pad9)") (class "Default")
      (node (ref "U10") (pin "9") (pinfunction "PA17_9") (pintype "passive"))
    )
    (net (code "194") (name "unconnected-(U10-PA28-Pad111)") (class "Default")
      (node (ref "U10") (pin "111") (pinfunction "PA28_111") (pintype "passive"))
    )
    (net (code "195") (name "unconnected-(U10-PB12-Pad86)") (class "Default")
      (node (ref "U10") (pin "86") (pinfunction "PB12_86") (pintype "passive"))
    )
    (net (code "196") (name "unconnected-(U10-PB13-Pad87)") (class "Default")
      (node (ref "U10") (pin "87") (pinfunction "PB13_87") (pintype "passive"))
    )
    (net (code "197") (name "unconnected-(U10-PB23-Pad142)") (class "Default")
      (node (ref "U10") (pin "142") (pinfunction "PB23_142") (pintype "passive"))
    )
    (net (code "198") (name "unconnected-(U10-PB24-Pad143)") (class "Default")
      (node (ref "U10") (pin "143") (pinfunction "PB24_143") (pintype "passive"))
    )
    (net (code "199") (name "unconnected-(U10-PB25-Pad144)") (class "Default")
      (node (ref "U10") (pin "144") (pinfunction "PB25_144") (pintype "passive"))
    )
    (net (code "200") (name "unconnected-(U10-PB26-Pad1)") (class "Default")
      (node (ref "U10") (pin "1") (pinfunction "PB26_1") (pintype "passive"))
    )
    (net (code "201") (name "unconnected-(U10-PC1-Pad55)") (class "Default")
      (node (ref "U10") (pin "55") (pinfunction "PC1_55") (pintype "passive"))
    )
    (net (code "202") (name "unconnected-(U10-PC4-Pad116)") (class "Default")
      (node (ref "U10") (pin "116") (pinfunction "PC4_116") (pintype "passive"))
    )
    (net (code "203") (name "unconnected-(U10-PC10-Pad117)") (class "Default")
      (node (ref "U10") (pin "117") (pinfunction "PC10_117") (pintype "passive"))
    )
    (net (code "204") (name "unconnected-(U10-PC21-Pad132)") (class "Default")
      (node (ref "U10") (pin "132") (pinfunction "PC21_132") (pintype "passive"))
    )
    (net (code "205") (name "unconnected-(U10-PC30-Pad103)") (class "Default")
      (node (ref "U10") (pin "103") (pinfunction "PC30_103") (pintype "passive"))
    )
    (net (code "206") (name "unconnected-(U10-PD8-Pad21)") (class "Default")
      (node (ref "U10") (pin "21") (pinfunction "PD8_21") (pintype "passive"))
    )
    (net (code "207") (name "unconnected-(U10-PD9-Pad22)") (class "Default")
      (node (ref "U10") (pin "22") (pinfunction "PD9_22") (pintype "passive"))
    )
    (net (code "208") (name "unconnected-(U10-PD10-Pad32)") (class "Default")
      (node (ref "U10") (pin "32") (pinfunction "PD10_32") (pintype "passive"))
    )
    (net (code "209") (name "unconnected-(U10-SHDN-Pad50)") (class "Default")
      (node (ref "U10") (pin "50") (pinfunction "SHDN_50") (pintype "output"))
    )
    (net (code "210") (name "unconnected-(U10-TST-Pad51)") (class "Default")
      (node (ref "U10") (pin "51") (pinfunction "TST_51") (pintype "passive"))
    )
    (net (code "211") (name "unconnected-(U11-VID-Pad11)") (class "Default")
      (node (ref "U11") (pin "11") (pinfunction "VID_11") (pintype "input+no_connect"))
    )
    (net (code "212") (name "unconnected-(U11-VOD-Pad6)") (class "Default")
      (node (ref "U11") (pin "6") (pinfunction "VOD_6") (pintype "tri_state+no_connect"))
    )
    (net (code "213") (name "unconnected-(X1-ID-Pad4)") (class "Default")
      (node (ref "X1") (pin "4") (pinfunction "ID_4") (pintype "passive"))
    )
  )
)
